# DC-DC.net
KiCad netlist of a schematic drawn in EAGLE
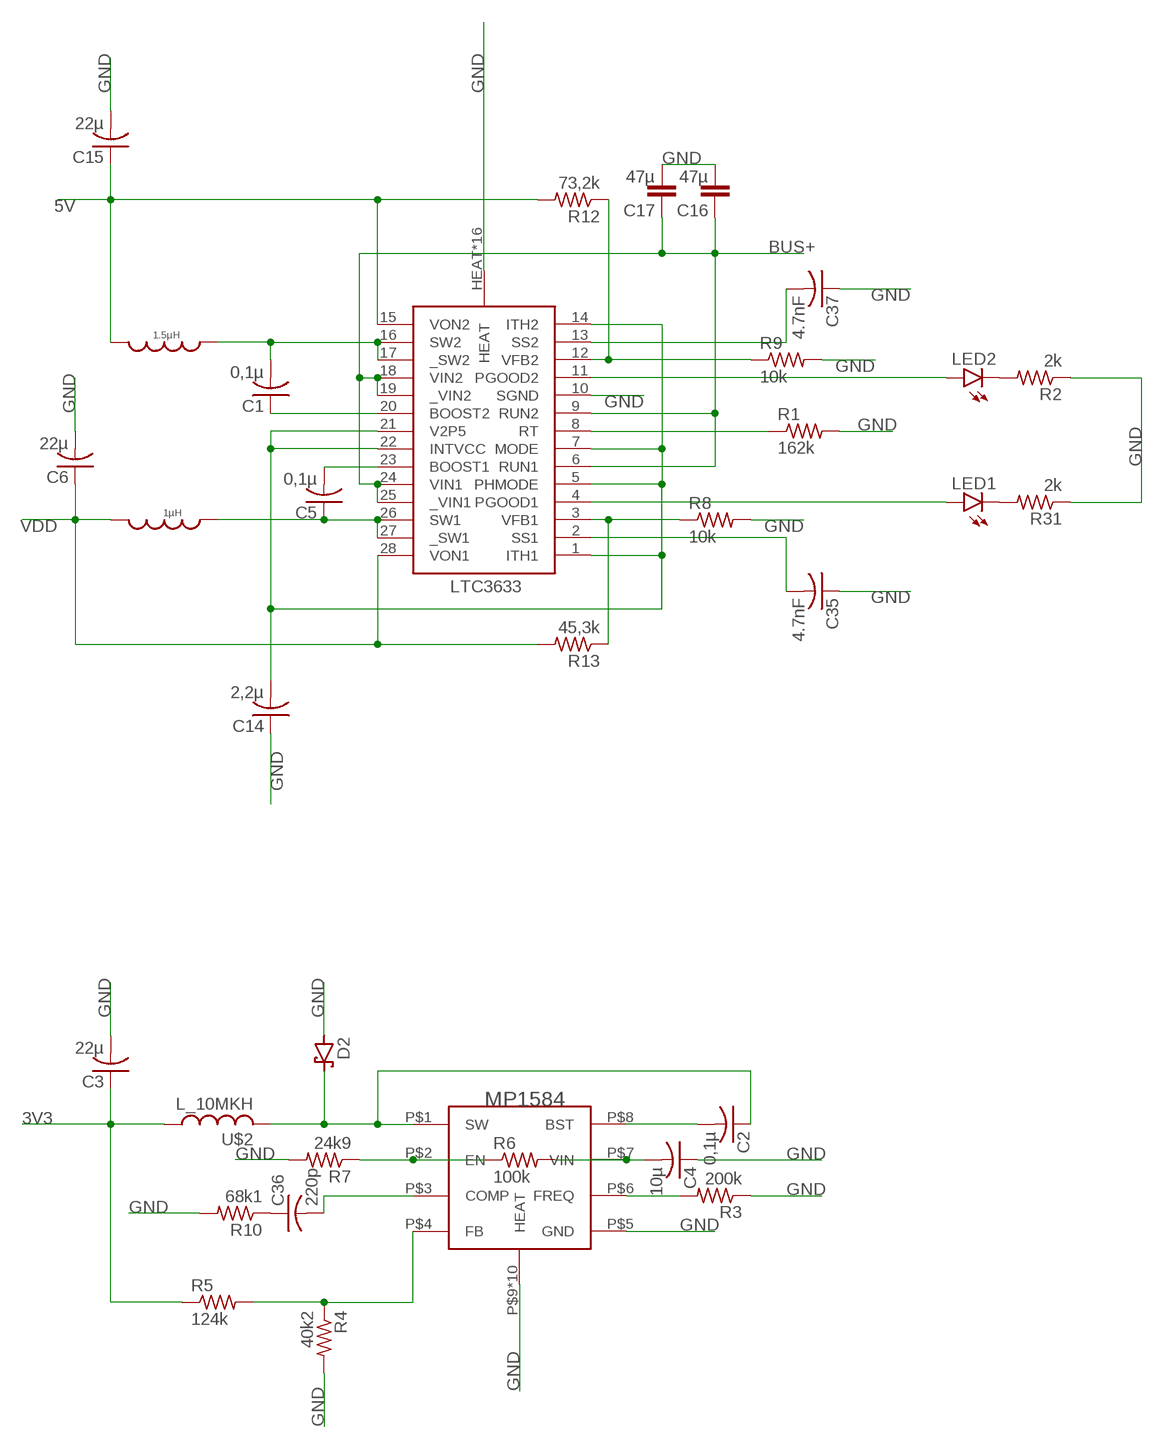
[diagram p0: schematic, sheet 1, part 1 of 3]
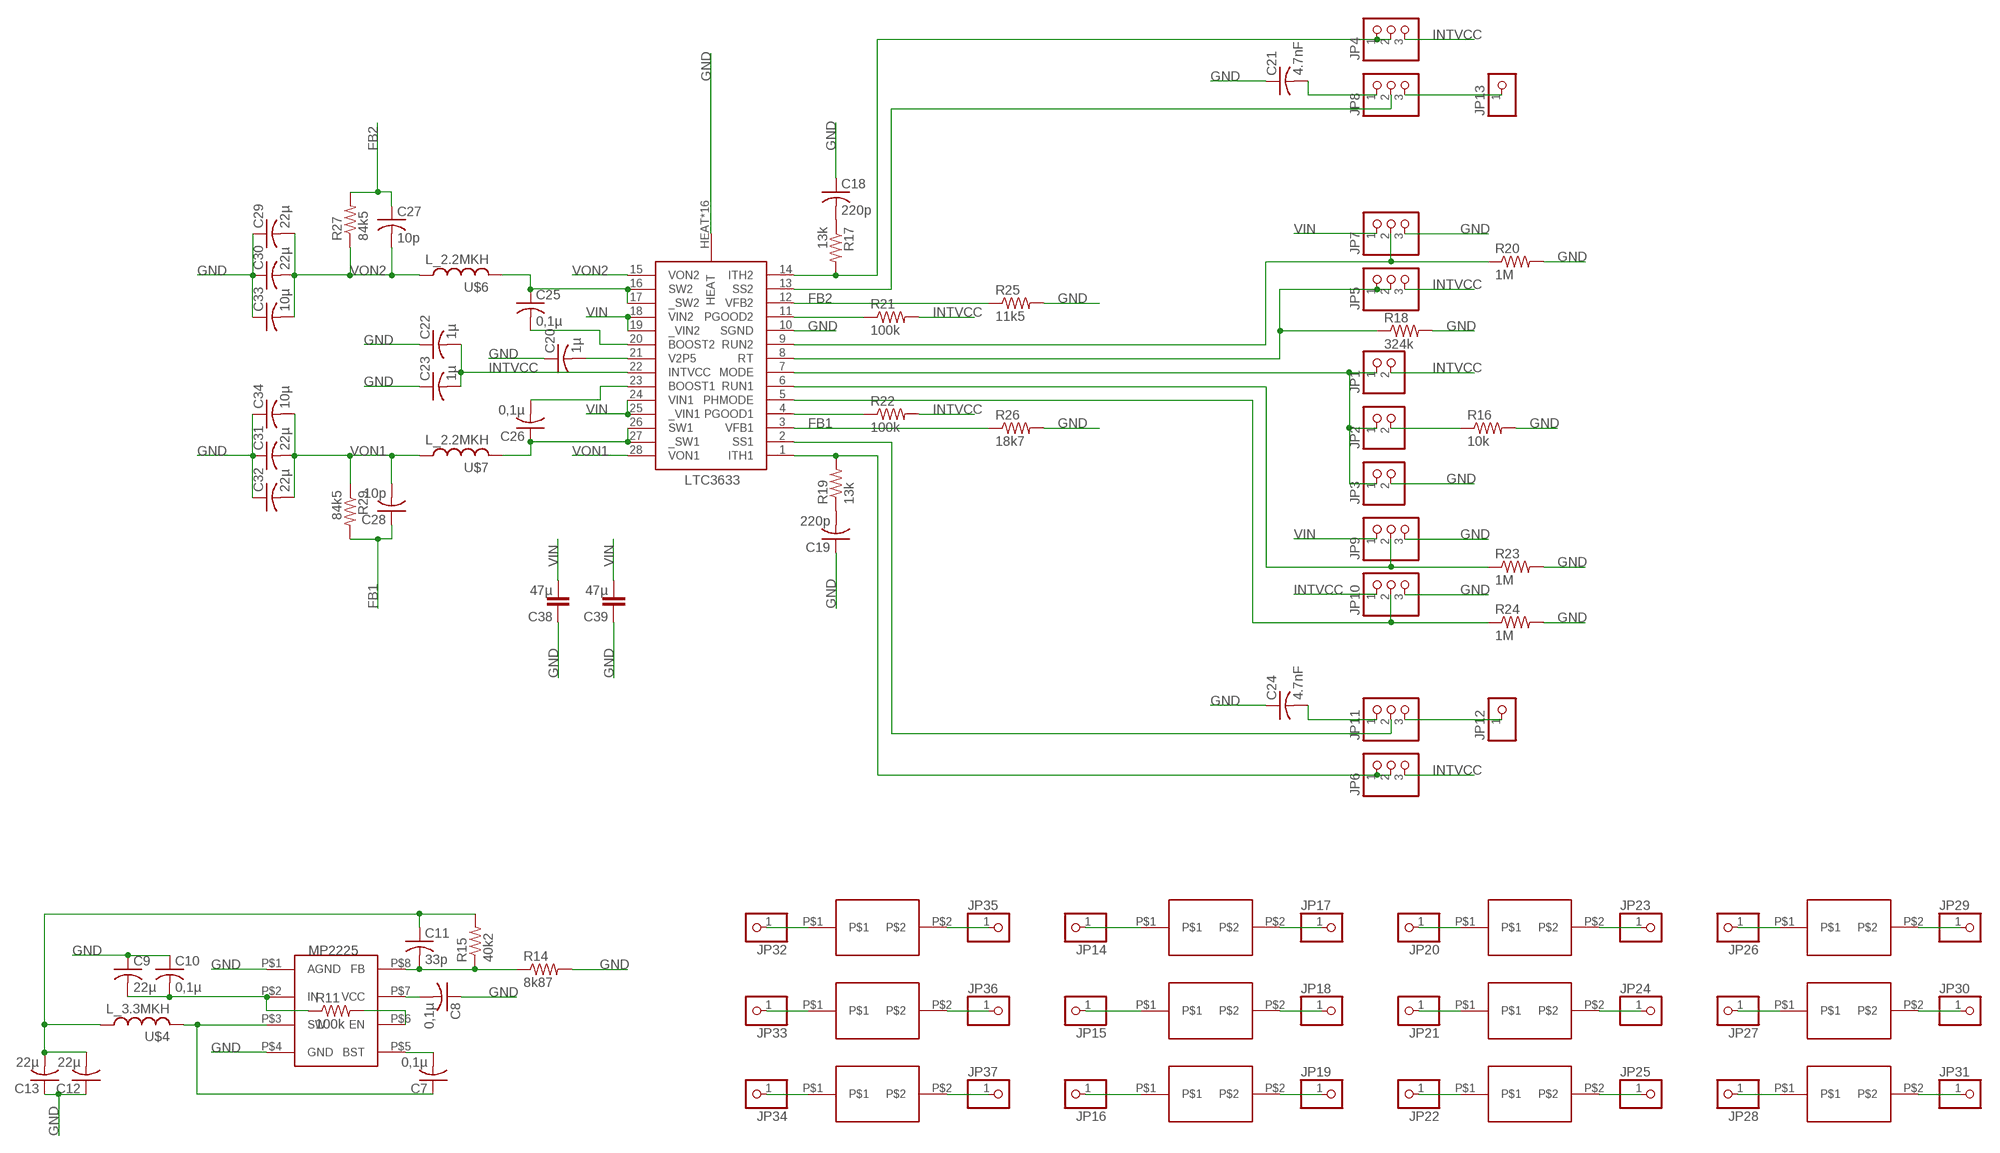
[diagram p1: schematic, sheet 1, part 2 of 3]
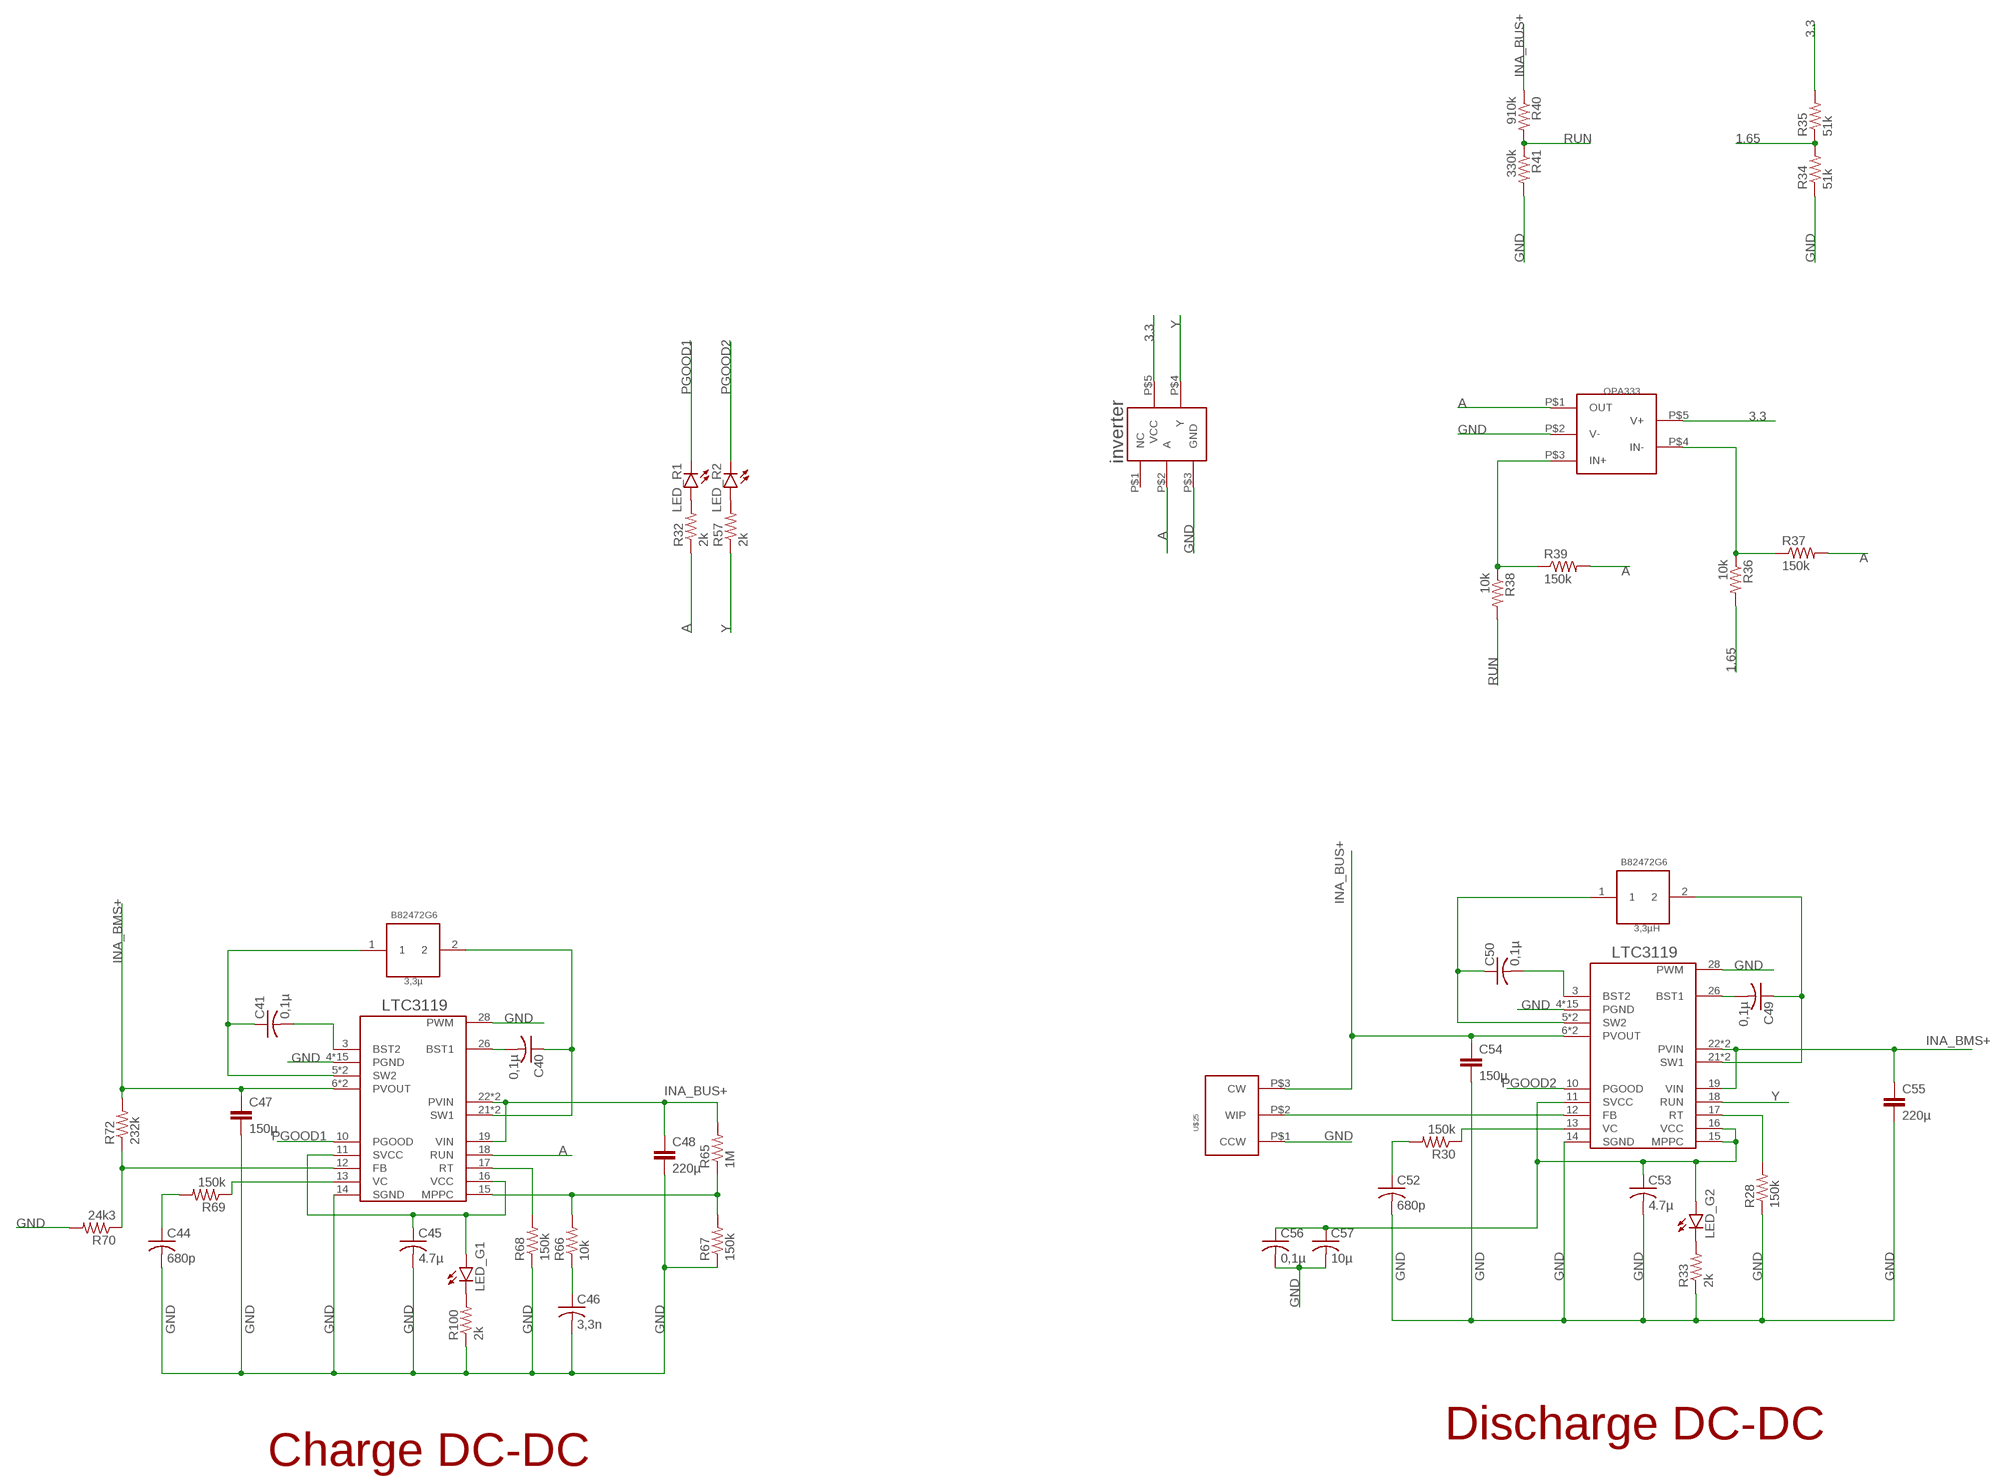
[diagram p2: schematic, sheet 1, part 3 of 3]

(export (version "E")
  (design (tool "Eeschema 10.0.6"))
  (components
    (comp (ref "3,3µH")
      (value "3,3µ")
      (footprint "eagle-import:B82472G6")
      (libsource (lib "eagle-import") (part "B82472G6"))
    )
    (comp (ref "3,3µH1")
      (value "3,3µH")
      (footprint "eagle-import:B82472G6")
      (libsource (lib "eagle-import") (part "B82472G6"))
    )
    (comp (ref "C1")
      (value "0,1µ")
      (footprint "eagle-import:C0603")
      (libsource (lib "eagle-import") (part "C-USC0603"))
    )
    (comp (ref "C2")
      (value "0,1µ")
      (footprint "eagle-import:C0603")
      (libsource (lib "eagle-import") (part "C-USC0603"))
    )
    (comp (ref "C3")
      (value "22µ")
      (footprint "eagle-import:C1206")
      (libsource (lib "eagle-import") (part "C-USC1206"))
    )
    (comp (ref "C4")
      (value "10µ")
      (footprint "eagle-import:C1206")
      (libsource (lib "eagle-import") (part "C-USC1206"))
    )
    (comp (ref "C5")
      (value "0,1µ")
      (footprint "eagle-import:C0603")
      (libsource (lib "eagle-import") (part "C-USC0603"))
    )
    (comp (ref "C6")
      (value "22µ")
      (footprint "eagle-import:C1206")
      (libsource (lib "eagle-import") (part "C-USC1206"))
    )
    (comp (ref "C7")
      (value "0,1µ")
      (footprint "eagle-import:C0603")
      (libsource (lib "eagle-import") (part "C-USC0603"))
    )
    (comp (ref "C8")
      (value "0,1µ")
      (footprint "eagle-import:C0603")
      (libsource (lib "eagle-import") (part "C-USC0603"))
    )
    (comp (ref "C9")
      (value "22µ")
      (footprint "eagle-import:C1206")
      (libsource (lib "eagle-import") (part "C-USC1206"))
    )
    (comp (ref "C10")
      (value "0,1µ")
      (footprint "eagle-import:C0603")
      (libsource (lib "eagle-import") (part "C-USC0603"))
    )
    (comp (ref "C11")
      (value "33p")
      (footprint "eagle-import:C0603")
      (libsource (lib "eagle-import") (part "C-USC0603"))
    )
    (comp (ref "C12")
      (value "22µ")
      (footprint "eagle-import:C1206")
      (libsource (lib "eagle-import") (part "C-USC1206"))
    )
    (comp (ref "C13")
      (value "22µ")
      (footprint "eagle-import:C1206")
      (libsource (lib "eagle-import") (part "C-USC1206"))
    )
    (comp (ref "C14")
      (value "2,2µ")
      (footprint "eagle-import:C0603")
      (libsource (lib "eagle-import") (part "C-USC0603"))
    )
    (comp (ref "C15")
      (value "22µ")
      (footprint "eagle-import:C1206")
      (libsource (lib "eagle-import") (part "C-USC1206"))
    )
    (comp (ref "C16")
      (value "47µ")
      (footprint "eagle-import:C1210")
      (libsource (lib "eagle-import") (part "C-EUC1210"))
    )
    (comp (ref "C17")
      (value "47µ")
      (footprint "eagle-import:C1210")
      (libsource (lib "eagle-import") (part "C-EUC1210"))
    )
    (comp (ref "C18")
      (value "220p")
      (footprint "eagle-import:C0603")
      (libsource (lib "eagle-import") (part "C-USC0603"))
    )
    (comp (ref "C19")
      (value "220p")
      (footprint "eagle-import:C0603")
      (libsource (lib "eagle-import") (part "C-USC0603"))
    )
    (comp (ref "C20")
      (value "1µ")
      (footprint "eagle-import:C0603")
      (libsource (lib "eagle-import") (part "C-USC0603"))
    )
    (comp (ref "C21")
      (value "4.7nF")
      (footprint "eagle-import:C0603")
      (libsource (lib "eagle-import") (part "C-USC0603"))
    )
    (comp (ref "C22")
      (value "1µ")
      (footprint "eagle-import:C0603")
      (libsource (lib "eagle-import") (part "C-USC0603"))
    )
    (comp (ref "C23")
      (value "1µ")
      (footprint "eagle-import:C0603")
      (libsource (lib "eagle-import") (part "C-USC0603"))
    )
    (comp (ref "C24")
      (value "4.7nF")
      (footprint "eagle-import:C0603")
      (libsource (lib "eagle-import") (part "C-USC0603"))
    )
    (comp (ref "C25")
      (value "0,1µ")
      (footprint "eagle-import:C0603")
      (libsource (lib "eagle-import") (part "C-USC0603"))
    )
    (comp (ref "C26")
      (value "0,1µ")
      (footprint "eagle-import:C0603")
      (libsource (lib "eagle-import") (part "C-USC0603"))
    )
    (comp (ref "C27")
      (value "10p")
      (footprint "eagle-import:C0603")
      (libsource (lib "eagle-import") (part "C-USC0603"))
    )
    (comp (ref "C28")
      (value "10p")
      (footprint "eagle-import:C0603")
      (libsource (lib "eagle-import") (part "C-USC0603"))
    )
    (comp (ref "C29")
      (value "22µ")
      (footprint "eagle-import:C1206")
      (libsource (lib "eagle-import") (part "C-USC1206"))
    )
    (comp (ref "C30")
      (value "22µ")
      (footprint "eagle-import:C1206")
      (libsource (lib "eagle-import") (part "C-USC1206"))
    )
    (comp (ref "C31")
      (value "22µ")
      (footprint "eagle-import:C1206")
      (libsource (lib "eagle-import") (part "C-USC1206"))
    )
    (comp (ref "C32")
      (value "22µ")
      (footprint "eagle-import:C1206")
      (libsource (lib "eagle-import") (part "C-USC1206"))
    )
    (comp (ref "C33")
      (value "10µ")
      (footprint "eagle-import:C1206")
      (libsource (lib "eagle-import") (part "C-USC1206"))
    )
    (comp (ref "C34")
      (value "10µ")
      (footprint "eagle-import:C1206")
      (libsource (lib "eagle-import") (part "C-USC1206"))
    )
    (comp (ref "C35")
      (value "4.7nF")
      (footprint "eagle-import:C0603")
      (libsource (lib "eagle-import") (part "C-USC0603"))
    )
    (comp (ref "C36")
      (value "220p")
      (footprint "eagle-import:C0603")
      (libsource (lib "eagle-import") (part "C-USC0603"))
    )
    (comp (ref "C37")
      (value "4.7nF")
      (footprint "eagle-import:C0603")
      (libsource (lib "eagle-import") (part "C-USC0603"))
    )
    (comp (ref "C38")
      (value "47µ")
      (footprint "eagle-import:C1210")
      (libsource (lib "eagle-import") (part "C-EUC1210"))
    )
    (comp (ref "C39")
      (value "47µ")
      (footprint "eagle-import:C1210")
      (libsource (lib "eagle-import") (part "C-EUC1210"))
    )
    (comp (ref "C40")
      (value "0,1µ")
      (footprint "eagle-import:C0603")
      (libsource (lib "eagle-import") (part "C-USC0603"))
    )
    (comp (ref "C41")
      (value "0,1µ")
      (footprint "eagle-import:C0603")
      (libsource (lib "eagle-import") (part "C-USC0603"))
    )
    (comp (ref "C44")
      (value "680p")
      (footprint "eagle-import:C0603")
      (libsource (lib "eagle-import") (part "C-USC0603"))
    )
    (comp (ref "C45")
      (value "4.7µ")
      (footprint "eagle-import:C1206")
      (libsource (lib "eagle-import") (part "C-USC1206"))
    )
    (comp (ref "C46")
      (value "3,3n")
      (footprint "eagle-import:C0603")
      (libsource (lib "eagle-import") (part "C-USC0603"))
    )
    (comp (ref "C47")
      (value "150µ")
      (footprint "eagle-import:ECAP150")
      (libsource (lib "eagle-import") (part "ECAPECAP150"))
    )
    (comp (ref "C48")
      (value "220µ")
      (footprint "eagle-import:ECAP220")
      (libsource (lib "eagle-import") (part "ECAPECAP220"))
    )
    (comp (ref "C49")
      (value "0,1µ")
      (footprint "eagle-import:C0603")
      (libsource (lib "eagle-import") (part "C-USC0603"))
    )
    (comp (ref "C50")
      (value "0,1µ")
      (footprint "eagle-import:C0603")
      (libsource (lib "eagle-import") (part "C-USC0603"))
    )
    (comp (ref "C52")
      (value "680p")
      (footprint "eagle-import:C0603")
      (libsource (lib "eagle-import") (part "C-USC0603"))
    )
    (comp (ref "C53")
      (value "4.7µ")
      (footprint "eagle-import:C1206")
      (libsource (lib "eagle-import") (part "C-USC1206"))
    )
    (comp (ref "C54")
      (value "150µ")
      (footprint "eagle-import:ECAP150")
      (libsource (lib "eagle-import") (part "ECAPECAP150"))
    )
    (comp (ref "C55")
      (value "220µ")
      (footprint "eagle-import:ECAP220")
      (libsource (lib "eagle-import") (part "ECAPECAP220"))
    )
    (comp (ref "C56")
      (value "0,1µ")
      (footprint "eagle-import:C0603")
      (libsource (lib "eagle-import") (part "C-USC0603"))
    )
    (comp (ref "C57")
      (value "10µ")
      (footprint "eagle-import:C1206")
      (libsource (lib "eagle-import") (part "C-USC1206"))
    )
    (comp (ref "D2")
      (value "SCHOTTKY-DIODESMC")
      (footprint "eagle-import:SMC")
      (libsource (lib "eagle-import") (part "SCHOTTKY-DIODESMC"))
    )
    (comp (ref "INVERT")
      (value "INVERTER")
      (footprint "eagle-import:SOT23-5")
      (libsource (lib "eagle-import") (part "INVERTER"))
    )
    (comp (ref "JP1")
      (value "PINHD-1X2")
      (footprint "eagle-import:1X02")
      (libsource (lib "eagle-import") (part "PINHD-1X2"))
    )
    (comp (ref "JP2")
      (value "PINHD-1X2")
      (footprint "eagle-import:1X02")
      (libsource (lib "eagle-import") (part "PINHD-1X2"))
    )
    (comp (ref "JP3")
      (value "PINHD-1X2")
      (footprint "eagle-import:1X02")
      (libsource (lib "eagle-import") (part "PINHD-1X2"))
    )
    (comp (ref "JP4")
      (value "PINHD-1X3")
      (footprint "eagle-import:1X03")
      (libsource (lib "eagle-import") (part "PINHD-1X3"))
    )
    (comp (ref "JP5")
      (value "PINHD-1X3")
      (footprint "eagle-import:1X03")
      (libsource (lib "eagle-import") (part "PINHD-1X3"))
    )
    (comp (ref "JP6")
      (value "PINHD-1X3")
      (footprint "eagle-import:1X03")
      (libsource (lib "eagle-import") (part "PINHD-1X3"))
    )
    (comp (ref "JP7")
      (value "PINHD-1X3")
      (footprint "eagle-import:1X03")
      (libsource (lib "eagle-import") (part "PINHD-1X3"))
    )
    (comp (ref "JP8")
      (value "PINHD-1X3")
      (footprint "eagle-import:1X03")
      (libsource (lib "eagle-import") (part "PINHD-1X3"))
    )
    (comp (ref "JP9")
      (value "PINHD-1X3")
      (footprint "eagle-import:1X03")
      (libsource (lib "eagle-import") (part "PINHD-1X3"))
    )
    (comp (ref "JP10")
      (value "PINHD-1X3")
      (footprint "eagle-import:1X03")
      (libsource (lib "eagle-import") (part "PINHD-1X3"))
    )
    (comp (ref "JP11")
      (value "PINHD-1X3")
      (footprint "eagle-import:1X03")
      (libsource (lib "eagle-import") (part "PINHD-1X3"))
    )
    (comp (ref "JP12")
      (value "PINHD-1X1")
      (footprint "eagle-import:1X01")
      (libsource (lib "eagle-import") (part "PINHD-1X1"))
    )
    (comp (ref "JP13")
      (value "PINHD-1X1")
      (footprint "eagle-import:1X01")
      (libsource (lib "eagle-import") (part "PINHD-1X1"))
    )
    (comp (ref "JP14")
      (value "PINHD-1X1")
      (footprint "eagle-import:1X01")
      (libsource (lib "eagle-import") (part "PINHD-1X1"))
    )
    (comp (ref "JP15")
      (value "PINHD-1X1")
      (footprint "eagle-import:1X01")
      (libsource (lib "eagle-import") (part "PINHD-1X1"))
    )
    (comp (ref "JP16")
      (value "PINHD-1X1")
      (footprint "eagle-import:1X01")
      (libsource (lib "eagle-import") (part "PINHD-1X1"))
    )
    (comp (ref "JP17")
      (value "PINHD-1X1")
      (footprint "eagle-import:1X01")
      (libsource (lib "eagle-import") (part "PINHD-1X1"))
    )
    (comp (ref "JP18")
      (value "PINHD-1X1")
      (footprint "eagle-import:1X01")
      (libsource (lib "eagle-import") (part "PINHD-1X1"))
    )
    (comp (ref "JP19")
      (value "PINHD-1X1")
      (footprint "eagle-import:1X01")
      (libsource (lib "eagle-import") (part "PINHD-1X1"))
    )
    (comp (ref "JP20")
      (value "PINHD-1X1")
      (footprint "eagle-import:1X01")
      (libsource (lib "eagle-import") (part "PINHD-1X1"))
    )
    (comp (ref "JP21")
      (value "PINHD-1X1")
      (footprint "eagle-import:1X01")
      (libsource (lib "eagle-import") (part "PINHD-1X1"))
    )
    (comp (ref "JP22")
      (value "PINHD-1X1")
      (footprint "eagle-import:1X01")
      (libsource (lib "eagle-import") (part "PINHD-1X1"))
    )
    (comp (ref "JP23")
      (value "PINHD-1X1")
      (footprint "eagle-import:1X01")
      (libsource (lib "eagle-import") (part "PINHD-1X1"))
    )
    (comp (ref "JP24")
      (value "PINHD-1X1")
      (footprint "eagle-import:1X01")
      (libsource (lib "eagle-import") (part "PINHD-1X1"))
    )
    (comp (ref "JP25")
      (value "PINHD-1X1")
      (footprint "eagle-import:1X01")
      (libsource (lib "eagle-import") (part "PINHD-1X1"))
    )
    (comp (ref "JP26")
      (value "PINHD-1X1")
      (footprint "eagle-import:1X01")
      (libsource (lib "eagle-import") (part "PINHD-1X1"))
    )
    (comp (ref "JP27")
      (value "PINHD-1X1")
      (footprint "eagle-import:1X01")
      (libsource (lib "eagle-import") (part "PINHD-1X1"))
    )
    (comp (ref "JP28")
      (value "PINHD-1X1")
      (footprint "eagle-import:1X01")
      (libsource (lib "eagle-import") (part "PINHD-1X1"))
    )
    (comp (ref "JP29")
      (value "PINHD-1X1")
      (footprint "eagle-import:1X01")
      (libsource (lib "eagle-import") (part "PINHD-1X1"))
    )
    (comp (ref "JP30")
      (value "PINHD-1X1")
      (footprint "eagle-import:1X01")
      (libsource (lib "eagle-import") (part "PINHD-1X1"))
    )
    (comp (ref "JP31")
      (value "PINHD-1X1")
      (footprint "eagle-import:1X01")
      (libsource (lib "eagle-import") (part "PINHD-1X1"))
    )
    (comp (ref "JP32")
      (value "PINHD-1X1")
      (footprint "eagle-import:1X01")
      (libsource (lib "eagle-import") (part "PINHD-1X1"))
    )
    (comp (ref "JP33")
      (value "PINHD-1X1")
      (footprint "eagle-import:1X01")
      (libsource (lib "eagle-import") (part "PINHD-1X1"))
    )
    (comp (ref "JP34")
      (value "PINHD-1X1")
      (footprint "eagle-import:1X01")
      (libsource (lib "eagle-import") (part "PINHD-1X1"))
    )
    (comp (ref "JP35")
      (value "PINHD-1X1")
      (footprint "eagle-import:1X01")
      (libsource (lib "eagle-import") (part "PINHD-1X1"))
    )
    (comp (ref "JP36")
      (value "PINHD-1X1")
      (footprint "eagle-import:1X01")
      (libsource (lib "eagle-import") (part "PINHD-1X1"))
    )
    (comp (ref "JP37")
      (value "PINHD-1X1")
      (footprint "eagle-import:1X01")
      (libsource (lib "eagle-import") (part "PINHD-1X1"))
    )
    (comp (ref "LED1")
      (value "LEDCHIPLED_0603")
      (footprint "eagle-import:CHIPLED_0603")
      (libsource (lib "eagle-import") (part "LEDCHIPLED_0603"))
    )
    (comp (ref "LED2")
      (value "LEDCHIPLED_0603")
      (footprint "eagle-import:CHIPLED_0603")
      (libsource (lib "eagle-import") (part "LEDCHIPLED_0603"))
    )
    (comp (ref "LED_G1")
      (value "LEDCHIPLED_0603")
      (footprint "eagle-import:CHIPLED_0603")
      (libsource (lib "eagle-import") (part "LEDCHIPLED_0603"))
    )
    (comp (ref "LED_G2")
      (value "LEDCHIPLED_0603")
      (footprint "eagle-import:CHIPLED_0603")
      (libsource (lib "eagle-import") (part "LEDCHIPLED_0603"))
    )
    (comp (ref "LED_R1")
      (value "LEDCHIPLED_0603")
      (footprint "eagle-import:CHIPLED_0603")
      (libsource (lib "eagle-import") (part "LEDCHIPLED_0603"))
    )
    (comp (ref "LED_R2")
      (value "LEDCHIPLED_0603")
      (footprint "eagle-import:CHIPLED_0603")
      (libsource (lib "eagle-import") (part "LEDCHIPLED_0603"))
    )
    (comp (ref "OPA")
      (value "OPA333")
      (footprint "eagle-import:SOT23-5")
      (libsource (lib "eagle-import") (part "OPA333"))
    )
    (comp (ref "R1")
      (value "162k")
      (footprint "eagle-import:R0603")
      (libsource (lib "eagle-import") (part "R-US_R0603"))
    )
    (comp (ref "R2")
      (value "2k")
      (footprint "eagle-import:R0603")
      (libsource (lib "eagle-import") (part "R-US_R0603"))
    )
    (comp (ref "R3")
      (value "200k")
      (footprint "eagle-import:R0603")
      (libsource (lib "eagle-import") (part "R-US_R0603"))
    )
    (comp (ref "R4")
      (value "40k2")
      (footprint "eagle-import:R0603")
      (libsource (lib "eagle-import") (part "R-US_R0603"))
    )
    (comp (ref "R5")
      (value "124k")
      (footprint "eagle-import:R0603")
      (libsource (lib "eagle-import") (part "R-US_R0603"))
    )
    (comp (ref "R6")
      (value "100k")
      (footprint "eagle-import:R0603")
      (libsource (lib "eagle-import") (part "R-US_R0603"))
    )
    (comp (ref "R7")
      (value "24k9")
      (footprint "eagle-import:R0603")
      (libsource (lib "eagle-import") (part "R-US_R0603"))
    )
    (comp (ref "R8")
      (value "10k")
      (footprint "eagle-import:R0603")
      (libsource (lib "eagle-import") (part "R-US_R0603"))
    )
    (comp (ref "R9")
      (value "10k")
      (footprint "eagle-import:R0603")
      (libsource (lib "eagle-import") (part "R-US_R0603"))
    )
    (comp (ref "R10")
      (value "68k1")
      (footprint "eagle-import:R0603")
      (libsource (lib "eagle-import") (part "R-US_R0603"))
    )
    (comp (ref "R11")
      (value "100k")
      (footprint "eagle-import:R0603")
      (libsource (lib "eagle-import") (part "R-US_R0603"))
    )
    (comp (ref "R12")
      (value "73,2k")
      (footprint "eagle-import:R0603")
      (libsource (lib "eagle-import") (part "R-US_R0603"))
    )
    (comp (ref "R13")
      (value "45,3k")
      (footprint "eagle-import:R0603")
      (libsource (lib "eagle-import") (part "R-US_R0603"))
    )
    (comp (ref "R14")
      (value "8k87")
      (footprint "eagle-import:R0603")
      (libsource (lib "eagle-import") (part "R-US_R0603"))
    )
    (comp (ref "R15")
      (value "40k2")
      (footprint "eagle-import:R0603")
      (libsource (lib "eagle-import") (part "R-US_R0603"))
    )
    (comp (ref "R16")
      (value "10k")
      (footprint "eagle-import:R0603")
      (libsource (lib "eagle-import") (part "R-US_R0603"))
    )
    (comp (ref "R17")
      (value "13k")
      (footprint "eagle-import:R0603")
      (libsource (lib "eagle-import") (part "R-US_R0603"))
    )
    (comp (ref "R18")
      (value "324k")
      (footprint "eagle-import:R0603")
      (libsource (lib "eagle-import") (part "R-US_R0603"))
    )
    (comp (ref "R19")
      (value "13k")
      (footprint "eagle-import:R0603")
      (libsource (lib "eagle-import") (part "R-US_R0603"))
    )
    (comp (ref "R20")
      (value "1M")
      (footprint "eagle-import:R0603")
      (libsource (lib "eagle-import") (part "R-US_R0603"))
    )
    (comp (ref "R21")
      (value "100k")
      (footprint "eagle-import:R0603")
      (libsource (lib "eagle-import") (part "R-US_R0603"))
    )
    (comp (ref "R22")
      (value "100k")
      (footprint "eagle-import:R0603")
      (libsource (lib "eagle-import") (part "R-US_R0603"))
    )
    (comp (ref "R23")
      (value "1M")
      (footprint "eagle-import:R0603")
      (libsource (lib "eagle-import") (part "R-US_R0603"))
    )
    (comp (ref "R24")
      (value "1M")
      (footprint "eagle-import:R0603")
      (libsource (lib "eagle-import") (part "R-US_R0603"))
    )
    (comp (ref "R25")
      (value "11k5")
      (footprint "eagle-import:R0603")
      (libsource (lib "eagle-import") (part "R-US_R0603"))
    )
    (comp (ref "R26")
      (value "18k7")
      (footprint "eagle-import:R0603")
      (libsource (lib "eagle-import") (part "R-US_R0603"))
    )
    (comp (ref "R27")
      (value "84k5")
      (footprint "eagle-import:R0603")
      (libsource (lib "eagle-import") (part "R-US_R0603"))
    )
    (comp (ref "R28")
      (value "150k")
      (footprint "eagle-import:R0603")
      (libsource (lib "eagle-import") (part "R-US_R0603"))
    )
    (comp (ref "R29")
      (value "84k5")
      (footprint "eagle-import:R0603")
      (libsource (lib "eagle-import") (part "R-US_R0603"))
    )
    (comp (ref "R30")
      (value "150k")
      (footprint "eagle-import:R0603")
      (libsource (lib "eagle-import") (part "R-US_R0603"))
    )
    (comp (ref "R31")
      (value "2k")
      (footprint "eagle-import:R0603")
      (libsource (lib "eagle-import") (part "R-US_R0603"))
    )
    (comp (ref "R32")
      (value "2k")
      (footprint "eagle-import:R0603")
      (libsource (lib "eagle-import") (part "R-US_R0603"))
    )
    (comp (ref "R33")
      (value "2k")
      (footprint "eagle-import:R0603")
      (libsource (lib "eagle-import") (part "R-US_R0603"))
    )
    (comp (ref "R34")
      (value "51k")
      (footprint "eagle-import:R0603")
      (libsource (lib "eagle-import") (part "R-US_R0603"))
    )
    (comp (ref "R35")
      (value "51k")
      (footprint "eagle-import:R0603")
      (libsource (lib "eagle-import") (part "R-US_R0603"))
    )
    (comp (ref "R36")
      (value "10k")
      (footprint "eagle-import:R0603")
      (libsource (lib "eagle-import") (part "R-US_R0603"))
    )
    (comp (ref "R37")
      (value "150k")
      (footprint "eagle-import:R0603")
      (libsource (lib "eagle-import") (part "R-US_R0603"))
    )
    (comp (ref "R38")
      (value "10k")
      (footprint "eagle-import:R0603")
      (libsource (lib "eagle-import") (part "R-US_R0603"))
    )
    (comp (ref "R39")
      (value "150k")
      (footprint "eagle-import:R0603")
      (libsource (lib "eagle-import") (part "R-US_R0603"))
    )
    (comp (ref "R40")
      (value "910k")
      (footprint "eagle-import:R0603")
      (libsource (lib "eagle-import") (part "R-US_R0603"))
    )
    (comp (ref "R41")
      (value "330k")
      (footprint "eagle-import:R0603")
      (libsource (lib "eagle-import") (part "R-US_R0603"))
    )
    (comp (ref "R57")
      (value "2k")
      (footprint "eagle-import:R0603")
      (libsource (lib "eagle-import") (part "R-US_R0603"))
    )
    (comp (ref "R65")
      (value "1M")
      (footprint "eagle-import:R0603")
      (libsource (lib "eagle-import") (part "R-US_R0603"))
    )
    (comp (ref "R66")
      (value "10k")
      (footprint "eagle-import:R0603")
      (libsource (lib "eagle-import") (part "R-US_R0603"))
    )
    (comp (ref "R67")
      (value "150k")
      (footprint "eagle-import:R0603")
      (libsource (lib "eagle-import") (part "R-US_R0603"))
    )
    (comp (ref "R68")
      (value "150k")
      (footprint "eagle-import:R0603")
      (libsource (lib "eagle-import") (part "R-US_R0603"))
    )
    (comp (ref "R69")
      (value "150k")
      (footprint "eagle-import:R0603")
      (libsource (lib "eagle-import") (part "R-US_R0603"))
    )
    (comp (ref "R70")
      (value "24k3")
      (footprint "eagle-import:R0603")
      (libsource (lib "eagle-import") (part "R-US_R0603"))
    )
    (comp (ref "R72")
      (value "232k")
      (footprint "eagle-import:R0603")
      (libsource (lib "eagle-import") (part "R-US_R0603"))
    )
    (comp (ref "R100")
      (value "2k")
      (footprint "eagle-import:R0603")
      (libsource (lib "eagle-import") (part "R-US_R0603"))
    )
    (comp (ref "U$1")
      (value "MP1584+VIA")
      (footprint "eagle-import:MP1584+VIA")
      (libsource (lib "eagle-import") (part "MP1584+VIA"))
    )
    (comp (ref "U$2")
      (value "L_10MKH")
      (footprint "eagle-import:L_12X12")
      (libsource (lib "eagle-import") (part "L_10MKH"))
    )
    (comp (ref "U$3")
      (value "MP2225")
      (footprint "eagle-import:TSOT23-8")
      (libsource (lib "eagle-import") (part "MP2225"))
    )
    (comp (ref "U$4")
      (value "L_3.3MKH")
      (footprint "eagle-import:L_SPM5020")
      (libsource (lib "eagle-import") (part "L_3.3MKH_5X5"))
    )
    (comp (ref "U$5")
      (value "LTC3633+VIA")
      (footprint "eagle-import:LTC3633+VIA")
      (libsource (lib "eagle-import") (part "LTC3633+VIA"))
    )
    (comp (ref "U$6")
      (value "L_2.2MKH")
      (footprint "eagle-import:L_SPM4020")
      (libsource (lib "eagle-import") (part "L_2.2MKH"))
    )
    (comp (ref "U$7")
      (value "L_2.2MKH")
      (footprint "eagle-import:L_SPM4020")
      (libsource (lib "eagle-import") (part "L_2.2MKH"))
    )
    (comp (ref "U$8")
      (value "GRAFITGRAFIT1")
      (footprint "eagle-import:GRAFIT1")
      (libsource (lib "eagle-import") (part "GRAFITGRAFIT1"))
    )
    (comp (ref "U$9")
      (value "GRAFITGRAFIT1_1")
      (footprint "eagle-import:GRAFIT1_1")
      (libsource (lib "eagle-import") (part "GRAFITGRAFIT1_1"))
    )
    (comp (ref "U$10")
      (value "LTC3633+VIA")
      (footprint "eagle-import:LTC3633+VIA")
      (libsource (lib "eagle-import") (part "LTC3633+VIA"))
    )
    (comp (ref "U$11")
      (value "1µH")
      (footprint "eagle-import:VLS3012HBX")
      (libsource (lib "eagle-import") (part "VLS3012HBX"))
    )
    (comp (ref "U$12")
      (value "SPM4020")
      (footprint "eagle-import:SPM4020")
      (libsource (lib "eagle-import") (part "SPM4020"))
    )
    (comp (ref "U$13")
      (value "GRAFITGRAFIT1_2")
      (footprint "eagle-import:GRAFIT1_2")
      (libsource (lib "eagle-import") (part "GRAFITGRAFIT1_2"))
    )
    (comp (ref "U$14")
      (value "GRAFITGRAFIT2")
      (footprint "eagle-import:GRAFIT2")
      (libsource (lib "eagle-import") (part "GRAFITGRAFIT2"))
    )
    (comp (ref "U$15")
      (value "GRAFITGRAFIT2_1")
      (footprint "eagle-import:GRAFIT2_1")
      (libsource (lib "eagle-import") (part "GRAFITGRAFIT2_1"))
    )
    (comp (ref "U$16")
      (value "GRAFITGRAFIT2_2")
      (footprint "eagle-import:GRAFIT2_2")
      (libsource (lib "eagle-import") (part "GRAFITGRAFIT2_2"))
    )
    (comp (ref "U$17")
      (value "GRAFITGRAFIT3")
      (footprint "eagle-import:GRAFIT3")
      (libsource (lib "eagle-import") (part "GRAFITGRAFIT3"))
    )
    (comp (ref "U$18")
      (value "GRAFITGRAFIT3_1")
      (footprint "eagle-import:GRAFIT3_1")
      (libsource (lib "eagle-import") (part "GRAFITGRAFIT3_1"))
    )
    (comp (ref "U$19")
      (value "GRAFITGRAFIT3_2")
      (footprint "eagle-import:GRAFIT3_2")
      (libsource (lib "eagle-import") (part "GRAFITGRAFIT3_2"))
    )
    (comp (ref "U$20")
      (value "GRAFITGRAFIT4")
      (footprint "eagle-import:GRAFIT4")
      (libsource (lib "eagle-import") (part "GRAFITGRAFIT4"))
    )
    (comp (ref "U$21")
      (value "GRAFITGRAFIT4_1")
      (footprint "eagle-import:GRAFIT4_1")
      (libsource (lib "eagle-import") (part "GRAFITGRAFIT4_1"))
    )
    (comp (ref "U$22")
      (value "GRAFITGRAFIT4_2")
      (footprint "eagle-import:GRAFIT4_2")
      (libsource (lib "eagle-import") (part "GRAFITGRAFIT4_2"))
    )
    (comp (ref "U$23")
      (value "LTC31191")
      (footprint "eagle-import:LTC3119+VIA")
      (libsource (lib "eagle-import") (part "LTC31191"))
    )
    (comp (ref "U$25")
      (value "32961")
      (footprint "eagle-import:3296W")
      (libsource (lib "eagle-import") (part "32961"))
    )
    (comp (ref "U$59")
      (value "LTC31191")
      (footprint "eagle-import:LTC3119+VIA")
      (libsource (lib "eagle-import") (part "LTC31191"))
    )
  )
  (nets
    (net (code "1") (name "/1.65") (class "Default")
      (node (ref "R34") (pin "2") (pinfunction "2_2") (pintype "passive"))
      (node (ref "R35") (pin "1") (pinfunction "1_1") (pintype "passive"))
      (node (ref "R36") (pin "2") (pinfunction "2_2") (pintype "passive"))
    )
    (net (code "2") (name "/3.3") (class "Default")
      (node (ref "INVERT") (pin "P$5") (pinfunction "VCC_P$5") (pintype "bidirectional"))
      (node (ref "OPA") (pin "P$5") (pinfunction "V+_P$5") (pintype "bidirectional"))
      (node (ref "R35") (pin "2") (pinfunction "2_2") (pintype "passive"))
    )
    (net (code "3") (name "/3V3") (class "Default")
      (node (ref "C3") (pin "1") (pinfunction "1_1") (pintype "passive"))
      (node (ref "R5") (pin "1") (pinfunction "1_1") (pintype "passive"))
      (node (ref "U$2") (pin "P$1") (pinfunction "1_P$1") (pintype "passive"))
    )
    (net (code "4") (name "/5V") (class "Default")
      (node (ref "C15") (pin "1") (pinfunction "1_1") (pintype "passive"))
      (node (ref "R12") (pin "2") (pinfunction "2_2") (pintype "passive"))
      (node (ref "U$10") (pin "15") (pinfunction "VON2_15") (pintype "bidirectional"))
      (node (ref "U$12") (pin "P$2") (pinfunction "2_P$2") (pintype "passive"))
    )
    (net (code "5") (name "/A") (class "Default")
      (node (ref "INVERT") (pin "P$2") (pinfunction "A_P$2") (pintype "bidirectional"))
      (node (ref "OPA") (pin "P$1") (pinfunction "OUT_P$1") (pintype "bidirectional"))
      (node (ref "R32") (pin "1") (pinfunction "1_1") (pintype "passive"))
      (node (ref "R37") (pin "2") (pinfunction "2_2") (pintype "passive"))
      (node (ref "R39") (pin "2") (pinfunction "2_2") (pintype "passive"))
      (node (ref "U$59") (pin "18") (pinfunction "RUN_18") (pintype "bidirectional"))
    )
    (net (code "6") (name "/BUS+") (class "Default")
      (node (ref "C16") (pin "1") (pinfunction "1_1") (pintype "passive"))
      (node (ref "C17") (pin "1") (pinfunction "1_1") (pintype "passive"))
      (node (ref "U$10") (pin "18") (pinfunction "VIN2_18") (pintype "bidirectional"))
      (node (ref "U$10") (pin "19") (pinfunction "_VIN2_19") (pintype "bidirectional"))
      (node (ref "U$10") (pin "24") (pinfunction "VIN1_24") (pintype "bidirectional"))
      (node (ref "U$10") (pin "25") (pinfunction "_VIN1_25") (pintype "bidirectional"))
      (node (ref "U$10") (pin "6") (pinfunction "RUN1_6") (pintype "bidirectional"))
      (node (ref "U$10") (pin "9") (pinfunction "RUN2_9") (pintype "bidirectional"))
    )
    (net (code "7") (name "/FB1") (class "Default")
      (node (ref "C28") (pin "1") (pinfunction "1_1") (pintype "passive"))
      (node (ref "R26") (pin "1") (pinfunction "1_1") (pintype "passive"))
      (node (ref "R29") (pin "2") (pinfunction "2_2") (pintype "passive"))
      (node (ref "U$5") (pin "3") (pinfunction "VFB1_3") (pintype "bidirectional"))
    )
    (net (code "8") (name "/FB2") (class "Default")
      (node (ref "C27") (pin "1") (pinfunction "1_1") (pintype "passive"))
      (node (ref "R25") (pin "1") (pinfunction "1_1") (pintype "passive"))
      (node (ref "R27") (pin "2") (pinfunction "2_2") (pintype "passive"))
      (node (ref "U$5") (pin "12") (pinfunction "VFB2_12") (pintype "bidirectional"))
    )
    (net (code "9") (name "/GND") (class "Default")
      (node (ref "C10") (pin "1") (pinfunction "1_1") (pintype "passive"))
      (node (ref "C12") (pin "1") (pinfunction "1_1") (pintype "passive"))
      (node (ref "C13") (pin "1") (pinfunction "1_1") (pintype "passive"))
      (node (ref "C14") (pin "1") (pinfunction "1_1") (pintype "passive"))
      (node (ref "C15") (pin "2") (pinfunction "2_2") (pintype "passive"))
      (node (ref "C16") (pin "2") (pinfunction "2_2") (pintype "passive"))
      (node (ref "C17") (pin "2") (pinfunction "2_2") (pintype "passive"))
      (node (ref "C18") (pin "1") (pinfunction "1_1") (pintype "passive"))
      (node (ref "C19") (pin "1") (pinfunction "1_1") (pintype "passive"))
      (node (ref "C20") (pin "1") (pinfunction "1_1") (pintype "passive"))
      (node (ref "C21") (pin "1") (pinfunction "1_1") (pintype "passive"))
      (node (ref "C22") (pin "1") (pinfunction "1_1") (pintype "passive"))
      (node (ref "C23") (pin "1") (pinfunction "1_1") (pintype "passive"))
      (node (ref "C24") (pin "1") (pinfunction "1_1") (pintype "passive"))
      (node (ref "C29") (pin "1") (pinfunction "1_1") (pintype "passive"))
      (node (ref "C3") (pin "2") (pinfunction "2_2") (pintype "passive"))
      (node (ref "C30") (pin "1") (pinfunction "1_1") (pintype "passive"))
      (node (ref "C31") (pin "1") (pinfunction "1_1") (pintype "passive"))
      (node (ref "C32") (pin "1") (pinfunction "1_1") (pintype "passive"))
      (node (ref "C33") (pin "1") (pinfunction "1_1") (pintype "passive"))
      (node (ref "C34") (pin "1") (pinfunction "1_1") (pintype "passive"))
      (node (ref "C35") (pin "1") (pinfunction "1_1") (pintype "passive"))
      (node (ref "C37") (pin "1") (pinfunction "1_1") (pintype "passive"))
      (node (ref "C38") (pin "1") (pinfunction "1_1") (pintype "passive"))
      (node (ref "C39") (pin "1") (pinfunction "1_1") (pintype "passive"))
      (node (ref "C4") (pin "1") (pinfunction "1_1") (pintype "passive"))
      (node (ref "C44") (pin "2") (pinfunction "2_2") (pintype "passive"))
      (node (ref "C45") (pin "2") (pinfunction "2_2") (pintype "passive"))
      (node (ref "C46") (pin "2") (pinfunction "2_2") (pintype "passive"))
      (node (ref "C47") (pin "P$2") (pinfunction "2_P$2") (pintype "passive"))
      (node (ref "C48") (pin "P$2") (pinfunction "2_P$2") (pintype "passive"))
      (node (ref "C52") (pin "2") (pinfunction "2_2") (pintype "passive"))
      (node (ref "C53") (pin "2") (pinfunction "2_2") (pintype "passive"))
      (node (ref "C54") (pin "P$2") (pinfunction "2_P$2") (pintype "passive"))
      (node (ref "C55") (pin "P$2") (pinfunction "2_P$2") (pintype "passive"))
      (node (ref "C56") (pin "2") (pinfunction "2_2") (pintype "passive"))
      (node (ref "C57") (pin "2") (pinfunction "2_2") (pintype "passive"))
      (node (ref "C6") (pin "2") (pinfunction "2_2") (pintype "passive"))
      (node (ref "C8") (pin "1") (pinfunction "1_1") (pintype "passive"))
      (node (ref "C9") (pin "1") (pinfunction "1_1") (pintype "passive"))
      (node (ref "D2") (pin "A") (pinfunction "A_A") (pintype "passive"))
      (node (ref "INVERT") (pin "P$3") (pinfunction "GND_P$3") (pintype "bidirectional"))
      (node (ref "JP10") (pin "3") (pinfunction "3_3") (pintype "passive"))
      (node (ref "JP3") (pin "2") (pinfunction "2_2") (pintype "passive"))
      (node (ref "JP7") (pin "3") (pinfunction "3_3") (pintype "passive"))
      (node (ref "JP9") (pin "3") (pinfunction "3_3") (pintype "passive"))
      (node (ref "OPA") (pin "P$2") (pinfunction "V-_P$2") (pintype "bidirectional"))
      (node (ref "R1") (pin "2") (pinfunction "2_2") (pintype "passive"))
      (node (ref "R10") (pin "2") (pinfunction "2_2") (pintype "passive"))
      (node (ref "R100") (pin "1") (pinfunction "1_1") (pintype "passive"))
      (node (ref "R14") (pin "2") (pinfunction "2_2") (pintype "passive"))
      (node (ref "R16") (pin "2") (pinfunction "2_2") (pintype "passive"))
      (node (ref "R18") (pin "2") (pinfunction "2_2") (pintype "passive"))
      (node (ref "R2") (pin "1") (pinfunction "1_1") (pintype "passive"))
      (node (ref "R20") (pin "2") (pinfunction "2_2") (pintype "passive"))
      (node (ref "R23") (pin "2") (pinfunction "2_2") (pintype "passive"))
      (node (ref "R24") (pin "2") (pinfunction "2_2") (pintype "passive"))
      (node (ref "R25") (pin "2") (pinfunction "2_2") (pintype "passive"))
      (node (ref "R26") (pin "2") (pinfunction "2_2") (pintype "passive"))
      (node (ref "R28") (pin "1") (pinfunction "1_1") (pintype "passive"))
      (node (ref "R3") (pin "1") (pinfunction "1_1") (pintype "passive"))
      (node (ref "R31") (pin "1") (pinfunction "1_1") (pintype "passive"))
      (node (ref "R33") (pin "1") (pinfunction "1_1") (pintype "passive"))
      (node (ref "R34") (pin "1") (pinfunction "1_1") (pintype "passive"))
      (node (ref "R4") (pin "2") (pinfunction "2_2") (pintype "passive"))
      (node (ref "R41") (pin "2") (pinfunction "2_2") (pintype "passive"))
      (node (ref "R67") (pin "1") (pinfunction "1_1") (pintype "passive"))
      (node (ref "R68") (pin "1") (pinfunction "1_1") (pintype "passive"))
      (node (ref "R7") (pin "2") (pinfunction "2_2") (pintype "passive"))
      (node (ref "R70") (pin "2") (pinfunction "2_2") (pintype "passive"))
      (node (ref "R8") (pin "2") (pinfunction "2_2") (pintype "passive"))
      (node (ref "R9") (pin "2") (pinfunction "2_2") (pintype "passive"))
      (node (ref "U$1") (pin "P$10") (pinfunction "HEAT_P$10") (pintype "bidirectional"))
      (node (ref "U$1") (pin "P$11") (pinfunction "HEAT_P$11") (pintype "bidirectional"))
      (node (ref "U$1") (pin "P$12") (pinfunction "HEAT_P$12") (pintype "bidirectional"))
      (node (ref "U$1") (pin "P$13") (pinfunction "HEAT_P$13") (pintype "bidirectional"))
      (node (ref "U$1") (pin "P$14") (pinfunction "HEAT_P$14") (pintype "bidirectional"))
      (node (ref "U$1") (pin "P$15") (pinfunction "HEAT_P$15") (pintype "bidirectional"))
      (node (ref "U$1") (pin "P$16") (pinfunction "HEAT_P$16") (pintype "bidirectional"))
      (node (ref "U$1") (pin "P$17") (pinfunction "HEAT_P$17") (pintype "bidirectional"))
      (node (ref "U$1") (pin "P$18") (pinfunction "HEAT_P$18") (pintype "bidirectional"))
      (node (ref "U$1") (pin "P$5") (pinfunction "GND_P$5") (pintype "bidirectional"))
      (node (ref "U$1") (pin "P$9") (pinfunction "HEAT_P$9") (pintype "bidirectional"))
      (node (ref "U$10") (pin "10") (pinfunction "SGND_10") (pintype "bidirectional"))
      (node (ref "U$10") (pin "HEAT") (pinfunction "HEAT_HEAT") (pintype "bidirectional"))
      (node (ref "U$10") (pin "P$1") (pinfunction "HEAT_P$1") (pintype "bidirectional"))
      (node (ref "U$10") (pin "P$10") (pinfunction "HEAT_P$10") (pintype "bidirectional"))
      (node (ref "U$10") (pin "P$11") (pinfunction "HEAT_P$11") (pintype "bidirectional"))
      (node (ref "U$10") (pin "P$12") (pinfunction "HEAT_P$12") (pintype "bidirectional"))
      (node (ref "U$10") (pin "P$13") (pinfunction "HEAT_P$13") (pintype "bidirectional"))
      (node (ref "U$10") (pin "P$14") (pinfunction "HEAT_P$14") (pintype "bidirectional"))
      (node (ref "U$10") (pin "P$15") (pinfunction "HEAT_P$15") (pintype "bidirectional"))
      (node (ref "U$10") (pin "P$2") (pinfunction "HEAT_P$2") (pintype "bidirectional"))
      (node (ref "U$10") (pin "P$3") (pinfunction "HEAT_P$3") (pintype "bidirectional"))
      (node (ref "U$10") (pin "P$4") (pinfunction "HEAT_P$4") (pintype "bidirectional"))
      (node (ref "U$10") (pin "P$5") (pinfunction "HEAT_P$5") (pintype "bidirectional"))
      (node (ref "U$10") (pin "P$6") (pinfunction "HEAT_P$6") (pintype "bidirectional"))
      (node (ref "U$10") (pin "P$7") (pinfunction "HEAT_P$7") (pintype "bidirectional"))
      (node (ref "U$10") (pin "P$8") (pinfunction "HEAT_P$8") (pintype "bidirectional"))
      (node (ref "U$10") (pin "P$9") (pinfunction "HEAT_P$9") (pintype "bidirectional"))
      (node (ref "U$23") (pin "14") (pinfunction "SGND_14") (pintype "bidirectional"))
      (node (ref "U$23") (pin "20") (pinfunction "PGND_20") (pintype "bidirectional"))
      (node (ref "U$23") (pin "25") (pinfunction "PGND_25") (pintype "bidirectional"))
      (node (ref "U$23") (pin "28") (pinfunction "PWM_28") (pintype "bidirectional"))
      (node (ref "U$23") (pin "29") (pinfunction "PGND_29") (pintype "bidirectional"))
      (node (ref "U$23") (pin "4") (pinfunction "PGND_4") (pintype "bidirectional"))
      (node (ref "U$23") (pin "9") (pinfunction "PGND_9") (pintype "bidirectional"))
      (node (ref "U$23") (pin "P$1") (pinfunction "PGND_P$1") (pintype "bidirectional"))
      (node (ref "U$23") (pin "P$10") (pinfunction "PGND_P$10") (pintype "bidirectional"))
      (node (ref "U$23") (pin "P$2") (pinfunction "PGND_P$2") (pintype "bidirectional"))
      (node (ref "U$23") (pin "P$3") (pinfunction "PGND_P$3") (pintype "bidirectional"))
      (node (ref "U$23") (pin "P$4") (pinfunction "PGND_P$4") (pintype "bidirectional"))
      (node (ref "U$23") (pin "P$5") (pinfunction "PGND_P$5") (pintype "bidirectional"))
      (node (ref "U$23") (pin "P$6") (pinfunction "PGND_P$6") (pintype "bidirectional"))
      (node (ref "U$23") (pin "P$7") (pinfunction "PGND_P$7") (pintype "bidirectional"))
      (node (ref "U$23") (pin "P$8") (pinfunction "PGND_P$8") (pintype "bidirectional"))
      (node (ref "U$23") (pin "P$9") (pinfunction "PGND_P$9") (pintype "bidirectional"))
      (node (ref "U$25") (pin "P$1") (pinfunction "CCW_P$1") (pintype "bidirectional"))
      (node (ref "U$3") (pin "P$1") (pinfunction "AGND_P$1") (pintype "bidirectional"))
      (node (ref "U$3") (pin "P$4") (pinfunction "GND_P$4") (pintype "bidirectional"))
      (node (ref "U$5") (pin "10") (pinfunction "SGND_10") (pintype "bidirectional"))
      (node (ref "U$5") (pin "HEAT") (pinfunction "HEAT_HEAT") (pintype "bidirectional"))
      (node (ref "U$5") (pin "P$1") (pinfunction "HEAT_P$1") (pintype "bidirectional"))
      (node (ref "U$5") (pin "P$10") (pinfunction "HEAT_P$10") (pintype "bidirectional"))
      (node (ref "U$5") (pin "P$11") (pinfunction "HEAT_P$11") (pintype "bidirectional"))
      (node (ref "U$5") (pin "P$12") (pinfunction "HEAT_P$12") (pintype "bidirectional"))
      (node (ref "U$5") (pin "P$13") (pinfunction "HEAT_P$13") (pintype "bidirectional"))
      (node (ref "U$5") (pin "P$14") (pinfunction "HEAT_P$14") (pintype "bidirectional"))
      (node (ref "U$5") (pin "P$15") (pinfunction "HEAT_P$15") (pintype "bidirectional"))
      (node (ref "U$5") (pin "P$2") (pinfunction "HEAT_P$2") (pintype "bidirectional"))
      (node (ref "U$5") (pin "P$3") (pinfunction "HEAT_P$3") (pintype "bidirectional"))
      (node (ref "U$5") (pin "P$4") (pinfunction "HEAT_P$4") (pintype "bidirectional"))
      (node (ref "U$5") (pin "P$5") (pinfunction "HEAT_P$5") (pintype "bidirectional"))
      (node (ref "U$5") (pin "P$6") (pinfunction "HEAT_P$6") (pintype "bidirectional"))
      (node (ref "U$5") (pin "P$7") (pinfunction "HEAT_P$7") (pintype "bidirectional"))
      (node (ref "U$5") (pin "P$8") (pinfunction "HEAT_P$8") (pintype "bidirectional"))
      (node (ref "U$5") (pin "P$9") (pinfunction "HEAT_P$9") (pintype "bidirectional"))
      (node (ref "U$59") (pin "14") (pinfunction "SGND_14") (pintype "bidirectional"))
      (node (ref "U$59") (pin "20") (pinfunction "PGND_20") (pintype "bidirectional"))
      (node (ref "U$59") (pin "25") (pinfunction "PGND_25") (pintype "bidirectional"))
      (node (ref "U$59") (pin "28") (pinfunction "PWM_28") (pintype "bidirectional"))
      (node (ref "U$59") (pin "29") (pinfunction "PGND_29") (pintype "bidirectional"))
      (node (ref "U$59") (pin "4") (pinfunction "PGND_4") (pintype "bidirectional"))
      (node (ref "U$59") (pin "9") (pinfunction "PGND_9") (pintype "bidirectional"))
      (node (ref "U$59") (pin "P$1") (pinfunction "PGND_P$1") (pintype "bidirectional"))
      (node (ref "U$59") (pin "P$10") (pinfunction "PGND_P$10") (pintype "bidirectional"))
      (node (ref "U$59") (pin "P$2") (pinfunction "PGND_P$2") (pintype "bidirectional"))
      (node (ref "U$59") (pin "P$3") (pinfunction "PGND_P$3") (pintype "bidirectional"))
      (node (ref "U$59") (pin "P$4") (pinfunction "PGND_P$4") (pintype "bidirectional"))
      (node (ref "U$59") (pin "P$5") (pinfunction "PGND_P$5") (pintype "bidirectional"))
      (node (ref "U$59") (pin "P$6") (pinfunction "PGND_P$6") (pintype "bidirectional"))
      (node (ref "U$59") (pin "P$7") (pinfunction "PGND_P$7") (pintype "bidirectional"))
      (node (ref "U$59") (pin "P$8") (pinfunction "PGND_P$8") (pintype "bidirectional"))
      (node (ref "U$59") (pin "P$9") (pinfunction "PGND_P$9") (pintype "bidirectional"))
    )
    (net (code "10") (name "/INA_BMS+") (class "Default")
      (node (ref "C47") (pin "P$1") (pinfunction "1_P$1") (pintype "passive"))
      (node (ref "C55") (pin "P$1") (pinfunction "1_P$1") (pintype "passive"))
      (node (ref "R72") (pin "2") (pinfunction "2_2") (pintype "passive"))
      (node (ref "U$23") (pin "19") (pinfunction "VIN_19") (pintype "bidirectional"))
      (node (ref "U$23") (pin "22") (pinfunction "PVIN_22") (pintype "bidirectional"))
      (node (ref "U$23") (pin "23") (pinfunction "PVIN_23") (pintype "bidirectional"))
      (node (ref "U$59") (pin "6") (pinfunction "PVOUT_6") (pintype "bidirectional"))
      (node (ref "U$59") (pin "7") (pinfunction "PVOUT_7") (pintype "bidirectional"))
    )
    (net (code "11") (name "/INA_BUS+") (class "Default")
      (node (ref "C48") (pin "P$1") (pinfunction "1_P$1") (pintype "passive"))
      (node (ref "C54") (pin "P$1") (pinfunction "1_P$1") (pintype "passive"))
      (node (ref "R40") (pin "1") (pinfunction "1_1") (pintype "passive"))
      (node (ref "R65") (pin "2") (pinfunction "2_2") (pintype "passive"))
      (node (ref "U$23") (pin "6") (pinfunction "PVOUT_6") (pintype "bidirectional"))
      (node (ref "U$23") (pin "7") (pinfunction "PVOUT_7") (pintype "bidirectional"))
      (node (ref "U$25") (pin "P$3") (pinfunction "CW_P$3") (pintype "bidirectional"))
      (node (ref "U$59") (pin "19") (pinfunction "VIN_19") (pintype "bidirectional"))
      (node (ref "U$59") (pin "22") (pinfunction "PVIN_22") (pintype "bidirectional"))
      (node (ref "U$59") (pin "23") (pinfunction "PVIN_23") (pintype "bidirectional"))
    )
    (net (code "12") (name "/INTVCC") (class "Default")
      (node (ref "C22") (pin "2") (pinfunction "2_2") (pintype "passive"))
      (node (ref "C23") (pin "2") (pinfunction "2_2") (pintype "passive"))
      (node (ref "JP1") (pin "2") (pinfunction "2_2") (pintype "passive"))
      (node (ref "JP10") (pin "1") (pinfunction "1_1") (pintype "passive"))
      (node (ref "JP4") (pin "3") (pinfunction "3_3") (pintype "passive"))
      (node (ref "JP5") (pin "3") (pinfunction "3_3") (pintype "passive"))
      (node (ref "JP6") (pin "3") (pinfunction "3_3") (pintype "passive"))
      (node (ref "R21") (pin "2") (pinfunction "2_2") (pintype "passive"))
      (node (ref "R22") (pin "2") (pinfunction "2_2") (pintype "passive"))
      (node (ref "U$5") (pin "22") (pinfunction "INTVCC_22") (pintype "bidirectional"))
    )
    (net (code "13") (name "/PGOOD1") (class "Default")
      (node (ref "LED_R1") (pin "C") (pinfunction "C_C") (pintype "passive"))
      (node (ref "U$59") (pin "10") (pinfunction "PGOOD_10") (pintype "bidirectional"))
    )
    (net (code "14") (name "/PGOOD2") (class "Default")
      (node (ref "LED_R2") (pin "C") (pinfunction "C_C") (pintype "passive"))
      (node (ref "U$23") (pin "10") (pinfunction "PGOOD_10") (pintype "bidirectional"))
    )
    (net (code "15") (name "/RUN") (class "Default")
      (node (ref "R38") (pin "2") (pinfunction "2_2") (pintype "passive"))
      (node (ref "R40") (pin "2") (pinfunction "2_2") (pintype "passive"))
      (node (ref "R41") (pin "1") (pinfunction "1_1") (pintype "passive"))
    )
    (net (code "16") (name "/VDD") (class "Default")
      (node (ref "C6") (pin "1") (pinfunction "1_1") (pintype "passive"))
      (node (ref "R13") (pin "2") (pinfunction "2_2") (pintype "passive"))
      (node (ref "U$10") (pin "28") (pinfunction "VON1_28") (pintype "bidirectional"))
      (node (ref "U$11") (pin "P$2") (pinfunction "2_P$2") (pintype "passive"))
    )
    (net (code "17") (name "/VIN") (class "Default")
      (node (ref "C38") (pin "2") (pinfunction "2_2") (pintype "passive"))
      (node (ref "C39") (pin "2") (pinfunction "2_2") (pintype "passive"))
      (node (ref "JP7") (pin "1") (pinfunction "1_1") (pintype "passive"))
      (node (ref "JP9") (pin "1") (pinfunction "1_1") (pintype "passive"))
      (node (ref "U$5") (pin "18") (pinfunction "VIN2_18") (pintype "bidirectional"))
      (node (ref "U$5") (pin "19") (pinfunction "_VIN2_19") (pintype "bidirectional"))
      (node (ref "U$5") (pin "24") (pinfunction "VIN1_24") (pintype "bidirectional"))
      (node (ref "U$5") (pin "25") (pinfunction "_VIN1_25") (pintype "bidirectional"))
    )
    (net (code "18") (name "/VON1") (class "Default")
      (node (ref "C28") (pin "2") (pinfunction "2_2") (pintype "passive"))
      (node (ref "C31") (pin "2") (pinfunction "2_2") (pintype "passive"))
      (node (ref "C32") (pin "2") (pinfunction "2_2") (pintype "passive"))
      (node (ref "C34") (pin "2") (pinfunction "2_2") (pintype "passive"))
      (node (ref "R29") (pin "1") (pinfunction "1_1") (pintype "passive"))
      (node (ref "U$5") (pin "28") (pinfunction "VON1_28") (pintype "bidirectional"))
      (node (ref "U$7") (pin "P$1") (pinfunction "1_P$1") (pintype "passive"))
    )
    (net (code "19") (name "/VON2") (class "Default")
      (node (ref "C27") (pin "2") (pinfunction "2_2") (pintype "passive"))
      (node (ref "C29") (pin "2") (pinfunction "2_2") (pintype "passive"))
      (node (ref "C30") (pin "2") (pinfunction "2_2") (pintype "passive"))
      (node (ref "C33") (pin "2") (pinfunction "2_2") (pintype "passive"))
      (node (ref "R27") (pin "1") (pinfunction "1_1") (pintype "passive"))
      (node (ref "U$5") (pin "15") (pinfunction "VON2_15") (pintype "bidirectional"))
      (node (ref "U$6") (pin "P$1") (pinfunction "1_P$1") (pintype "passive"))
    )
    (net (code "20") (name "/Y") (class "Default")
      (node (ref "INVERT") (pin "P$4") (pinfunction "Y_P$4") (pintype "bidirectional"))
      (node (ref "R57") (pin "1") (pinfunction "1_1") (pintype "passive"))
      (node (ref "U$23") (pin "18") (pinfunction "RUN_18") (pintype "bidirectional"))
    )
    (net (code "21") (name "Net-(3,3µH-Pad1)") (class "Default")
      (node (ref "3,3µH") (pin "1") (pinfunction "1_1") (pintype "bidirectional"))
      (node (ref "C41") (pin "1") (pinfunction "1_1") (pintype "passive"))
      (node (ref "U$59") (pin "5") (pinfunction "SW2_5") (pintype "bidirectional"))
      (node (ref "U$59") (pin "8") (pinfunction "SW2_8") (pintype "bidirectional"))
    )
    (net (code "22") (name "Net-(3,3µH-Pad2)") (class "Default")
      (node (ref "3,3µH") (pin "2") (pinfunction "2_2") (pintype "bidirectional"))
      (node (ref "C40") (pin "1") (pinfunction "1_1") (pintype "passive"))
      (node (ref "U$59") (pin "21") (pinfunction "SW1_21") (pintype "bidirectional"))
      (node (ref "U$59") (pin "24") (pinfunction "SW1_24") (pintype "bidirectional"))
    )
    (net (code "23") (name "Net-(3,3µH1-Pad1)") (class "Default")
      (node (ref "3,3µH1") (pin "1") (pinfunction "1_1") (pintype "bidirectional"))
      (node (ref "C50") (pin "1") (pinfunction "1_1") (pintype "passive"))
      (node (ref "U$23") (pin "5") (pinfunction "SW2_5") (pintype "bidirectional"))
      (node (ref "U$23") (pin "8") (pinfunction "SW2_8") (pintype "bidirectional"))
    )
    (net (code "24") (name "Net-(3,3µH1-Pad2)") (class "Default")
      (node (ref "3,3µH1") (pin "2") (pinfunction "2_2") (pintype "bidirectional"))
      (node (ref "C49") (pin "1") (pinfunction "1_1") (pintype "passive"))
      (node (ref "U$23") (pin "21") (pinfunction "SW1_21") (pintype "bidirectional"))
      (node (ref "U$23") (pin "24") (pinfunction "SW1_24") (pintype "bidirectional"))
    )
    (net (code "25") (name "Net-(C18-Pad2)") (class "Default")
      (node (ref "C18") (pin "2") (pinfunction "2_2") (pintype "passive"))
      (node (ref "R17") (pin "1") (pinfunction "1_1") (pintype "passive"))
    )
    (net (code "26") (name "Net-(C19-Pad2)") (class "Default")
      (node (ref "C19") (pin "2") (pinfunction "2_2") (pintype "passive"))
      (node (ref "R19") (pin "1") (pinfunction "1_1") (pintype "passive"))
    )
    (net (code "27") (name "Net-(C21-Pad2)") (class "Default")
      (node (ref "C21") (pin "2") (pinfunction "2_2") (pintype "passive"))
      (node (ref "JP8") (pin "1") (pinfunction "1_1") (pintype "passive"))
    )
    (net (code "28") (name "Net-(C24-Pad2)") (class "Default")
      (node (ref "C24") (pin "2") (pinfunction "2_2") (pintype "passive"))
      (node (ref "JP11") (pin "1") (pinfunction "1_1") (pintype "passive"))
    )
    (net (code "29") (name "Net-(C36-Pad1)") (class "Default")
      (node (ref "C36") (pin "1") (pinfunction "1_1") (pintype "passive"))
      (node (ref "R10") (pin "1") (pinfunction "1_1") (pintype "passive"))
    )
    (net (code "30") (name "Net-(C44-Pad1)") (class "Default")
      (node (ref "C44") (pin "1") (pinfunction "1_1") (pintype "passive"))
      (node (ref "R69") (pin "2") (pinfunction "2_2") (pintype "passive"))
    )
    (net (code "31") (name "Net-(C46-Pad1)") (class "Default")
      (node (ref "C46") (pin "1") (pinfunction "1_1") (pintype "passive"))
      (node (ref "R66") (pin "1") (pinfunction "1_1") (pintype "passive"))
    )
    (net (code "32") (name "Net-(C52-Pad1)") (class "Default")
      (node (ref "C52") (pin "1") (pinfunction "1_1") (pintype "passive"))
      (node (ref "R30") (pin "2") (pinfunction "2_2") (pintype "passive"))
    )
    (net (code "33") (name "Net-(JP2-Pad2)") (class "Default")
      (node (ref "JP2") (pin "2") (pinfunction "2_2") (pintype "passive"))
      (node (ref "R16") (pin "1") (pinfunction "1_1") (pintype "passive"))
    )
    (net (code "34") (name "Net-(JP11-Pad3)") (class "Default")
      (node (ref "JP11") (pin "3") (pinfunction "3_3") (pintype "passive"))
      (node (ref "JP12") (pin "1") (pinfunction "1_1") (pintype "passive"))
    )
    (net (code "35") (name "Net-(JP13-Pad1)") (class "Default")
      (node (ref "JP13") (pin "1") (pinfunction "1_1") (pintype "passive"))
      (node (ref "JP8") (pin "3") (pinfunction "3_3") (pintype "passive"))
    )
    (net (code "36") (name "Net-(JP14-Pad1)") (class "Default")
      (node (ref "JP14") (pin "1") (pinfunction "1_1") (pintype "passive"))
      (node (ref "U$14") (pin "P$1") (pinfunction "P$1_P$1") (pintype "bidirectional"))
    )
    (net (code "37") (name "Net-(JP15-Pad1)") (class "Default")
      (node (ref "JP15") (pin "1") (pinfunction "1_1") (pintype "passive"))
      (node (ref "U$15") (pin "P$1") (pinfunction "P$1_P$1") (pintype "bidirectional"))
    )
    (net (code "38") (name "Net-(JP16-Pad1)") (class "Default")
      (node (ref "JP16") (pin "1") (pinfunction "1_1") (pintype "passive"))
      (node (ref "U$16") (pin "P$1") (pinfunction "P$1_P$1") (pintype "bidirectional"))
    )
    (net (code "39") (name "Net-(JP17-Pad1)") (class "Default")
      (node (ref "JP17") (pin "1") (pinfunction "1_1") (pintype "passive"))
      (node (ref "U$14") (pin "P$2") (pinfunction "P$2_P$2") (pintype "bidirectional"))
    )
    (net (code "40") (name "Net-(JP18-Pad1)") (class "Default")
      (node (ref "JP18") (pin "1") (pinfunction "1_1") (pintype "passive"))
      (node (ref "U$15") (pin "P$2") (pinfunction "P$2_P$2") (pintype "bidirectional"))
    )
    (net (code "41") (name "Net-(JP19-Pad1)") (class "Default")
      (node (ref "JP19") (pin "1") (pinfunction "1_1") (pintype "passive"))
      (node (ref "U$16") (pin "P$2") (pinfunction "P$2_P$2") (pintype "bidirectional"))
    )
    (net (code "42") (name "Net-(JP20-Pad1)") (class "Default")
      (node (ref "JP20") (pin "1") (pinfunction "1_1") (pintype "passive"))
      (node (ref "U$17") (pin "P$1") (pinfunction "P$1_P$1") (pintype "bidirectional"))
    )
    (net (code "43") (name "Net-(JP21-Pad1)") (class "Default")
      (node (ref "JP21") (pin "1") (pinfunction "1_1") (pintype "passive"))
      (node (ref "U$18") (pin "P$1") (pinfunction "P$1_P$1") (pintype "bidirectional"))
    )
    (net (code "44") (name "Net-(JP22-Pad1)") (class "Default")
      (node (ref "JP22") (pin "1") (pinfunction "1_1") (pintype "passive"))
      (node (ref "U$19") (pin "P$1") (pinfunction "P$1_P$1") (pintype "bidirectional"))
    )
    (net (code "45") (name "Net-(JP23-Pad1)") (class "Default")
      (node (ref "JP23") (pin "1") (pinfunction "1_1") (pintype "passive"))
      (node (ref "U$17") (pin "P$2") (pinfunction "P$2_P$2") (pintype "bidirectional"))
    )
    (net (code "46") (name "Net-(JP24-Pad1)") (class "Default")
      (node (ref "JP24") (pin "1") (pinfunction "1_1") (pintype "passive"))
      (node (ref "U$18") (pin "P$2") (pinfunction "P$2_P$2") (pintype "bidirectional"))
    )
    (net (code "47") (name "Net-(JP25-Pad1)") (class "Default")
      (node (ref "JP25") (pin "1") (pinfunction "1_1") (pintype "passive"))
      (node (ref "U$19") (pin "P$2") (pinfunction "P$2_P$2") (pintype "bidirectional"))
    )
    (net (code "48") (name "Net-(JP26-Pad1)") (class "Default")
      (node (ref "JP26") (pin "1") (pinfunction "1_1") (pintype "passive"))
      (node (ref "U$20") (pin "P$1") (pinfunction "P$1_P$1") (pintype "bidirectional"))
    )
    (net (code "49") (name "Net-(JP27-Pad1)") (class "Default")
      (node (ref "JP27") (pin "1") (pinfunction "1_1") (pintype "passive"))
      (node (ref "U$21") (pin "P$1") (pinfunction "P$1_P$1") (pintype "bidirectional"))
    )
    (net (code "50") (name "Net-(JP28-Pad1)") (class "Default")
      (node (ref "JP28") (pin "1") (pinfunction "1_1") (pintype "passive"))
      (node (ref "U$22") (pin "P$1") (pinfunction "P$1_P$1") (pintype "bidirectional"))
    )
    (net (code "51") (name "Net-(JP29-Pad1)") (class "Default")
      (node (ref "JP29") (pin "1") (pinfunction "1_1") (pintype "passive"))
      (node (ref "U$20") (pin "P$2") (pinfunction "P$2_P$2") (pintype "bidirectional"))
    )
    (net (code "52") (name "Net-(JP30-Pad1)") (class "Default")
      (node (ref "JP30") (pin "1") (pinfunction "1_1") (pintype "passive"))
      (node (ref "U$21") (pin "P$2") (pinfunction "P$2_P$2") (pintype "bidirectional"))
    )
    (net (code "53") (name "Net-(JP31-Pad1)") (class "Default")
      (node (ref "JP31") (pin "1") (pinfunction "1_1") (pintype "passive"))
      (node (ref "U$22") (pin "P$2") (pinfunction "P$2_P$2") (pintype "bidirectional"))
    )
    (net (code "54") (name "Net-(JP32-Pad1)") (class "Default")
      (node (ref "JP32") (pin "1") (pinfunction "1_1") (pintype "passive"))
      (node (ref "U$8") (pin "P$1") (pinfunction "P$1_P$1") (pintype "bidirectional"))
    )
    (net (code "55") (name "Net-(JP33-Pad1)") (class "Default")
      (node (ref "JP33") (pin "1") (pinfunction "1_1") (pintype "passive"))
      (node (ref "U$9") (pin "P$1") (pinfunction "P$1_P$1") (pintype "bidirectional"))
    )
    (net (code "56") (name "Net-(JP34-Pad1)") (class "Default")
      (node (ref "JP34") (pin "1") (pinfunction "1_1") (pintype "passive"))
      (node (ref "U$13") (pin "P$1") (pinfunction "P$1_P$1") (pintype "bidirectional"))
    )
    (net (code "57") (name "Net-(JP35-Pad1)") (class "Default")
      (node (ref "JP35") (pin "1") (pinfunction "1_1") (pintype "passive"))
      (node (ref "U$8") (pin "P$2") (pinfunction "P$2_P$2") (pintype "bidirectional"))
    )
    (net (code "58") (name "Net-(JP36-Pad1)") (class "Default")
      (node (ref "JP36") (pin "1") (pinfunction "1_1") (pintype "passive"))
      (node (ref "U$9") (pin "P$2") (pinfunction "P$2_P$2") (pintype "bidirectional"))
    )
    (net (code "59") (name "Net-(JP37-Pad1)") (class "Default")
      (node (ref "JP37") (pin "1") (pinfunction "1_1") (pintype "passive"))
      (node (ref "U$13") (pin "P$2") (pinfunction "P$2_P$2") (pintype "bidirectional"))
    )
    (net (code "60") (name "Net-(LED1-PadC)") (class "Default")
      (node (ref "LED1") (pin "C") (pinfunction "C_C") (pintype "passive"))
      (node (ref "R31") (pin "2") (pinfunction "2_2") (pintype "passive"))
    )
    (net (code "61") (name "Net-(LED2-PadC)") (class "Default")
      (node (ref "LED2") (pin "C") (pinfunction "C_C") (pintype "passive"))
      (node (ref "R2") (pin "2") (pinfunction "2_2") (pintype "passive"))
    )
    (net (code "62") (name "Net-(LED_G1-PadC)") (class "Default")
      (node (ref "LED_G1") (pin "C") (pinfunction "C_C") (pintype "passive"))
      (node (ref "R100") (pin "2") (pinfunction "2_2") (pintype "passive"))
    )
    (net (code "63") (name "Net-(LED_G2-PadC)") (class "Default")
      (node (ref "LED_G2") (pin "C") (pinfunction "C_C") (pintype "passive"))
      (node (ref "R33") (pin "2") (pinfunction "2_2") (pintype "passive"))
    )
    (net (code "64") (name "Net-(LED_R1-PadA)") (class "Default")
      (node (ref "LED_R1") (pin "A") (pinfunction "A_A") (pintype "passive"))
      (node (ref "R32") (pin "2") (pinfunction "2_2") (pintype "passive"))
    )
    (net (code "65") (name "Net-(LED_R2-PadA)") (class "Default")
      (node (ref "LED_R2") (pin "A") (pinfunction "A_A") (pintype "passive"))
      (node (ref "R57") (pin "2") (pinfunction "2_2") (pintype "passive"))
    )
    (net (code "66") (name "Net-(OPA-IN+)") (class "Default")
      (node (ref "OPA") (pin "P$3") (pinfunction "IN+_P$3") (pintype "bidirectional"))
      (node (ref "R38") (pin "1") (pinfunction "1_1") (pintype "passive"))
      (node (ref "R39") (pin "1") (pinfunction "1_1") (pintype "passive"))
    )
    (net (code "67") (name "Net-(OPA-IN-)") (class "Default")
      (node (ref "OPA") (pin "P$4") (pinfunction "IN-_P$4") (pintype "bidirectional"))
      (node (ref "R36") (pin "1") (pinfunction "1_1") (pintype "passive"))
      (node (ref "R37") (pin "1") (pinfunction "1_1") (pintype "passive"))
    )
    (net (code "68") (name "Net-(U$1-BST)") (class "Default")
      (node (ref "C2") (pin "2") (pinfunction "2_2") (pintype "passive"))
      (node (ref "U$1") (pin "P$8") (pinfunction "BST_P$8") (pintype "bidirectional"))
    )
    (net (code "69") (name "Net-(U$1-COMP)") (class "Default")
      (node (ref "C36") (pin "2") (pinfunction "2_2") (pintype "passive"))
      (node (ref "U$1") (pin "P$3") (pinfunction "COMP_P$3") (pintype "bidirectional"))
    )
    (net (code "70") (name "Net-(U$1-EN)") (class "Default")
      (node (ref "R6") (pin "1") (pinfunction "1_1") (pintype "passive"))
      (node (ref "R7") (pin "1") (pinfunction "1_1") (pintype "passive"))
      (node (ref "U$1") (pin "P$2") (pinfunction "EN_P$2") (pintype "bidirectional"))
    )
    (net (code "71") (name "Net-(U$1-FB)") (class "Default")
      (node (ref "R4") (pin "1") (pinfunction "1_1") (pintype "passive"))
      (node (ref "R5") (pin "2") (pinfunction "2_2") (pintype "passive"))
      (node (ref "U$1") (pin "P$4") (pinfunction "FB_P$4") (pintype "bidirectional"))
    )
    (net (code "72") (name "Net-(U$1-FREQ)") (class "Default")
      (node (ref "R3") (pin "2") (pinfunction "2_2") (pintype "passive"))
      (node (ref "U$1") (pin "P$6") (pinfunction "FREQ_P$6") (pintype "bidirectional"))
    )
    (net (code "73") (name "Net-(U$1-SW)") (class "Default")
      (node (ref "C2") (pin "1") (pinfunction "1_1") (pintype "passive"))
      (node (ref "D2") (pin "C") (pinfunction "C_C") (pintype "passive"))
      (node (ref "U$1") (pin "P$1") (pinfunction "SW_P$1") (pintype "bidirectional"))
      (node (ref "U$2") (pin "P$2") (pinfunction "2_P$2") (pintype "passive"))
    )
    (net (code "74") (name "Net-(U$1-VIN)") (class "Default")
      (node (ref "C4") (pin "2") (pinfunction "2_2") (pintype "passive"))
      (node (ref "R6") (pin "2") (pinfunction "2_2") (pintype "passive"))
      (node (ref "U$1") (pin "P$7") (pinfunction "VIN_P$7") (pintype "bidirectional"))
    )
    (net (code "75") (name "Net-(U$3-BST)") (class "Default")
      (node (ref "C7") (pin "2") (pinfunction "2_2") (pintype "passive"))
      (node (ref "U$3") (pin "P$5") (pinfunction "BST_P$5") (pintype "bidirectional"))
    )
    (net (code "76") (name "Net-(U$3-EN)") (class "Default")
      (node (ref "R11") (pin "2") (pinfunction "2_2") (pintype "passive"))
      (node (ref "U$3") (pin "P$6") (pinfunction "EN_P$6") (pintype "bidirectional"))
    )
    (net (code "77") (name "Net-(U$3-FB)") (class "Default")
      (node (ref "C11") (pin "2") (pinfunction "2_2") (pintype "passive"))
      (node (ref "R14") (pin "1") (pinfunction "1_1") (pintype "passive"))
      (node (ref "R15") (pin "1") (pinfunction "1_1") (pintype "passive"))
      (node (ref "U$3") (pin "P$8") (pinfunction "FB_P$8") (pintype "bidirectional"))
    )
    (net (code "78") (name "Net-(U$3-IN)") (class "Default")
      (node (ref "C10") (pin "2") (pinfunction "2_2") (pintype "passive"))
      (node (ref "C9") (pin "2") (pinfunction "2_2") (pintype "passive"))
      (node (ref "R11") (pin "1") (pinfunction "1_1") (pintype "passive"))
      (node (ref "U$3") (pin "P$2") (pinfunction "IN_P$2") (pintype "bidirectional"))
    )
    (net (code "79") (name "Net-(U$3-SW)") (class "Default")
      (node (ref "C7") (pin "1") (pinfunction "1_1") (pintype "passive"))
      (node (ref "U$3") (pin "P$3") (pinfunction "SW_P$3") (pintype "bidirectional"))
      (node (ref "U$4") (pin "P$2") (pinfunction "2_P$2") (pintype "passive"))
    )
    (net (code "80") (name "Net-(U$3-VCC)") (class "Default")
      (node (ref "C8") (pin "2") (pinfunction "2_2") (pintype "passive"))
      (node (ref "U$3") (pin "P$7") (pinfunction "VCC_P$7") (pintype "bidirectional"))
    )
    (net (code "81") (name "Net-(U$4-1)") (class "Default")
      (node (ref "C11") (pin "1") (pinfunction "1_1") (pintype "passive"))
      (node (ref "C12") (pin "2") (pinfunction "2_2") (pintype "passive"))
      (node (ref "C13") (pin "2") (pinfunction "2_2") (pintype "passive"))
      (node (ref "R15") (pin "2") (pinfunction "2_2") (pintype "passive"))
      (node (ref "U$4") (pin "P$1") (pinfunction "1_P$1") (pintype "passive"))
    )
    (net (code "82") (name "Net-(U$5-BOOST1)") (class "Default")
      (node (ref "C26") (pin "2") (pinfunction "2_2") (pintype "passive"))
      (node (ref "U$5") (pin "23") (pinfunction "BOOST1_23") (pintype "bidirectional"))
    )
    (net (code "83") (name "Net-(U$5-BOOST2)") (class "Default")
      (node (ref "C25") (pin "2") (pinfunction "2_2") (pintype "passive"))
      (node (ref "U$5") (pin "20") (pinfunction "BOOST2_20") (pintype "bidirectional"))
    )
    (net (code "84") (name "Net-(U$5-ITH1)") (class "Default")
      (node (ref "JP6") (pin "1") (pinfunction "1_1") (pintype "passive"))
      (node (ref "JP6") (pin "2") (pinfunction "2_2") (pintype "passive"))
      (node (ref "R19") (pin "2") (pinfunction "2_2") (pintype "passive"))
      (node (ref "U$5") (pin "1") (pinfunction "ITH1_1") (pintype "bidirectional"))
    )
    (net (code "85") (name "Net-(U$5-ITH2)") (class "Default")
      (node (ref "JP4") (pin "1") (pinfunction "1_1") (pintype "passive"))
      (node (ref "JP4") (pin "2") (pinfunction "2_2") (pintype "passive"))
      (node (ref "R17") (pin "2") (pinfunction "2_2") (pintype "passive"))
      (node (ref "U$5") (pin "14") (pinfunction "ITH2_14") (pintype "bidirectional"))
    )
    (net (code "86") (name "Net-(U$5-MODE)") (class "Default")
      (node (ref "JP1") (pin "1") (pinfunction "1_1") (pintype "passive"))
      (node (ref "JP2") (pin "1") (pinfunction "1_1") (pintype "passive"))
      (node (ref "JP3") (pin "1") (pinfunction "1_1") (pintype "passive"))
      (node (ref "U$5") (pin "7") (pinfunction "MODE_7") (pintype "bidirectional"))
    )
    (net (code "87") (name "Net-(U$5-PGOOD1)") (class "Default")
      (node (ref "R22") (pin "1") (pinfunction "1_1") (pintype "passive"))
      (node (ref "U$5") (pin "4") (pinfunction "PGOOD1_4") (pintype "bidirectional"))
    )
    (net (code "88") (name "Net-(U$5-PGOOD2)") (class "Default")
      (node (ref "R21") (pin "1") (pinfunction "1_1") (pintype "passive"))
      (node (ref "U$5") (pin "11") (pinfunction "PGOOD2_11") (pintype "bidirectional"))
    )
    (net (code "89") (name "Net-(U$5-PHMODE)") (class "Default")
      (node (ref "JP10") (pin "2") (pinfunction "2_2") (pintype "passive"))
      (node (ref "R24") (pin "1") (pinfunction "1_1") (pintype "passive"))
      (node (ref "U$5") (pin "5") (pinfunction "PHMODE_5") (pintype "bidirectional"))
    )
    (net (code "90") (name "Net-(U$5-RT)") (class "Default")
      (node (ref "JP5") (pin "1") (pinfunction "1_1") (pintype "passive"))
      (node (ref "JP5") (pin "2") (pinfunction "2_2") (pintype "passive"))
      (node (ref "R18") (pin "1") (pinfunction "1_1") (pintype "passive"))
      (node (ref "U$5") (pin "8") (pinfunction "RT_8") (pintype "bidirectional"))
    )
    (net (code "91") (name "Net-(U$5-RUN1)") (class "Default")
      (node (ref "JP9") (pin "2") (pinfunction "2_2") (pintype "passive"))
      (node (ref "R23") (pin "1") (pinfunction "1_1") (pintype "passive"))
      (node (ref "U$5") (pin "6") (pinfunction "RUN1_6") (pintype "bidirectional"))
    )
    (net (code "92") (name "Net-(U$5-RUN2)") (class "Default")
      (node (ref "JP7") (pin "2") (pinfunction "2_2") (pintype "passive"))
      (node (ref "R20") (pin "1") (pinfunction "1_1") (pintype "passive"))
      (node (ref "U$5") (pin "9") (pinfunction "RUN2_9") (pintype "bidirectional"))
    )
    (net (code "93") (name "Net-(U$5-SS1)") (class "Default")
      (node (ref "JP11") (pin "2") (pinfunction "2_2") (pintype "passive"))
      (node (ref "U$5") (pin "2") (pinfunction "SS1_2") (pintype "bidirectional"))
    )
    (net (code "94") (name "Net-(U$5-SS2)") (class "Default")
      (node (ref "JP8") (pin "2") (pinfunction "2_2") (pintype "passive"))
      (node (ref "U$5") (pin "13") (pinfunction "SS2_13") (pintype "bidirectional"))
    )
    (net (code "95") (name "Net-(U$5-SW1)") (class "Default")
      (node (ref "C26") (pin "1") (pinfunction "1_1") (pintype "passive"))
      (node (ref "U$5") (pin "26") (pinfunction "SW1_26") (pintype "bidirectional"))
      (node (ref "U$5") (pin "27") (pinfunction "_SW1_27") (pintype "bidirectional"))
      (node (ref "U$7") (pin "P$2") (pinfunction "2_P$2") (pintype "passive"))
    )
    (net (code "96") (name "Net-(U$5-SW2)") (class "Default")
      (node (ref "C25") (pin "1") (pinfunction "1_1") (pintype "passive"))
      (node (ref "U$5") (pin "16") (pinfunction "SW2_16") (pintype "bidirectional"))
      (node (ref "U$5") (pin "17") (pinfunction "_SW2_17") (pintype "bidirectional"))
      (node (ref "U$6") (pin "P$2") (pinfunction "2_P$2") (pintype "passive"))
    )
    (net (code "97") (name "Net-(U$5-V2P5)") (class "Default")
      (node (ref "C20") (pin "2") (pinfunction "2_2") (pintype "passive"))
      (node (ref "U$5") (pin "21") (pinfunction "V2P5_21") (pintype "bidirectional"))
    )
    (net (code "98") (name "Net-(U$10-BOOST1)") (class "Default")
      (node (ref "C5") (pin "2") (pinfunction "2_2") (pintype "passive"))
      (node (ref "U$10") (pin "23") (pinfunction "BOOST1_23") (pintype "bidirectional"))
    )
    (net (code "99") (name "Net-(U$10-BOOST2)") (class "Default")
      (node (ref "C1") (pin "1") (pinfunction "1_1") (pintype "passive"))
      (node (ref "U$10") (pin "20") (pinfunction "BOOST2_20") (pintype "bidirectional"))
    )
    (net (code "100") (name "Net-(U$10-INTVCC)") (class "Default")
      (node (ref "C14") (pin "2") (pinfunction "2_2") (pintype "passive"))
      (node (ref "U$10") (pin "1") (pinfunction "ITH1_1") (pintype "bidirectional"))
      (node (ref "U$10") (pin "14") (pinfunction "ITH2_14") (pintype "bidirectional"))
      (node (ref "U$10") (pin "21") (pinfunction "V2P5_21") (pintype "bidirectional"))
      (node (ref "U$10") (pin "22") (pinfunction "INTVCC_22") (pintype "bidirectional"))
      (node (ref "U$10") (pin "5") (pinfunction "PHMODE_5") (pintype "bidirectional"))
      (node (ref "U$10") (pin "7") (pinfunction "MODE_7") (pintype "bidirectional"))
    )
    (net (code "101") (name "Net-(U$10-PGOOD1)") (class "Default")
      (node (ref "LED1") (pin "A") (pinfunction "A_A") (pintype "passive"))
      (node (ref "U$10") (pin "4") (pinfunction "PGOOD1_4") (pintype "bidirectional"))
    )
    (net (code "102") (name "Net-(U$10-PGOOD2)") (class "Default")
      (node (ref "LED2") (pin "A") (pinfunction "A_A") (pintype "passive"))
      (node (ref "U$10") (pin "11") (pinfunction "PGOOD2_11") (pintype "bidirectional"))
    )
    (net (code "103") (name "Net-(U$10-RT)") (class "Default")
      (node (ref "R1") (pin "1") (pinfunction "1_1") (pintype "passive"))
      (node (ref "U$10") (pin "8") (pinfunction "RT_8") (pintype "bidirectional"))
    )
    (net (code "104") (name "Net-(U$10-SS1)") (class "Default")
      (node (ref "C35") (pin "2") (pinfunction "2_2") (pintype "passive"))
      (node (ref "U$10") (pin "2") (pinfunction "SS1_2") (pintype "bidirectional"))
    )
    (net (code "105") (name "Net-(U$10-SS2)") (class "Default")
      (node (ref "C37") (pin "2") (pinfunction "2_2") (pintype "passive"))
      (node (ref "U$10") (pin "13") (pinfunction "SS2_13") (pintype "bidirectional"))
    )
    (net (code "106") (name "Net-(U$10-SW1)") (class "Default")
      (node (ref "C5") (pin "1") (pinfunction "1_1") (pintype "passive"))
      (node (ref "U$10") (pin "26") (pinfunction "SW1_26") (pintype "bidirectional"))
      (node (ref "U$10") (pin "27") (pinfunction "_SW1_27") (pintype "bidirectional"))
      (node (ref "U$11") (pin "P$1") (pinfunction "1_P$1") (pintype "passive"))
    )
    (net (code "107") (name "Net-(U$10-SW2)") (class "Default")
      (node (ref "C1") (pin "2") (pinfunction "2_2") (pintype "passive"))
      (node (ref "U$10") (pin "16") (pinfunction "SW2_16") (pintype "bidirectional"))
      (node (ref "U$10") (pin "17") (pinfunction "_SW2_17") (pintype "bidirectional"))
      (node (ref "U$12") (pin "P$1") (pinfunction "1_P$1") (pintype "passive"))
    )
    (net (code "108") (name "Net-(U$10-VFB1)") (class "Default")
      (node (ref "R13") (pin "1") (pinfunction "1_1") (pintype "passive"))
      (node (ref "R8") (pin "1") (pinfunction "1_1") (pintype "passive"))
      (node (ref "U$10") (pin "3") (pinfunction "VFB1_3") (pintype "bidirectional"))
    )
    (net (code "109") (name "Net-(U$10-VFB2)") (class "Default")
      (node (ref "R12") (pin "1") (pinfunction "1_1") (pintype "passive"))
      (node (ref "R9") (pin "1") (pinfunction "1_1") (pintype "passive"))
      (node (ref "U$10") (pin "12") (pinfunction "VFB2_12") (pintype "bidirectional"))
    )
    (net (code "110") (name "Net-(U$23-BST1)") (class "Default")
      (node (ref "C49") (pin "2") (pinfunction "2_2") (pintype "passive"))
      (node (ref "U$23") (pin "26") (pinfunction "BST1_26") (pintype "bidirectional"))
    )
    (net (code "111") (name "Net-(U$23-BST2)") (class "Default")
      (node (ref "C50") (pin "2") (pinfunction "2_2") (pintype "passive"))
      (node (ref "U$23") (pin "3") (pinfunction "BST2_3") (pintype "bidirectional"))
    )
    (net (code "112") (name "Net-(U$23-FB)") (class "Default")
      (node (ref "U$23") (pin "12") (pinfunction "FB_12") (pintype "bidirectional"))
      (node (ref "U$25") (pin "P$2") (pinfunction "WIP_P$2") (pintype "bidirectional"))
    )
    (net (code "113") (name "Net-(U$23-MPPC)") (class "Default")
      (node (ref "C53") (pin "1") (pinfunction "1_1") (pintype "passive"))
      (node (ref "C56") (pin "1") (pinfunction "1_1") (pintype "passive"))
      (node (ref "C57") (pin "1") (pinfunction "1_1") (pintype "passive"))
      (node (ref "LED_G2") (pin "A") (pinfunction "A_A") (pintype "passive"))
      (node (ref "U$23") (pin "11") (pinfunction "SVCC_11") (pintype "bidirectional"))
      (node (ref "U$23") (pin "15") (pinfunction "MPPC_15") (pintype "bidirectional"))
      (node (ref "U$23") (pin "16") (pinfunction "VCC_16") (pintype "bidirectional"))
    )
    (net (code "114") (name "Net-(U$23-RT)") (class "Default")
      (node (ref "R28") (pin "2") (pinfunction "2_2") (pintype "passive"))
      (node (ref "U$23") (pin "17") (pinfunction "RT_17") (pintype "bidirectional"))
    )
    (net (code "115") (name "Net-(U$23-VC)") (class "Default")
      (node (ref "R30") (pin "1") (pinfunction "1_1") (pintype "passive"))
      (node (ref "U$23") (pin "13") (pinfunction "VC_13") (pintype "bidirectional"))
    )
    (net (code "116") (name "Net-(U$59-BST1)") (class "Default")
      (node (ref "C40") (pin "2") (pinfunction "2_2") (pintype "passive"))
      (node (ref "U$59") (pin "26") (pinfunction "BST1_26") (pintype "bidirectional"))
    )
    (net (code "117") (name "Net-(U$59-BST2)") (class "Default")
      (node (ref "C41") (pin "2") (pinfunction "2_2") (pintype "passive"))
      (node (ref "U$59") (pin "3") (pinfunction "BST2_3") (pintype "bidirectional"))
    )
    (net (code "118") (name "Net-(U$59-FB)") (class "Default")
      (node (ref "R70") (pin "1") (pinfunction "1_1") (pintype "passive"))
      (node (ref "R72") (pin "1") (pinfunction "1_1") (pintype "passive"))
      (node (ref "U$59") (pin "12") (pinfunction "FB_12") (pintype "bidirectional"))
    )
    (net (code "119") (name "Net-(U$59-MPPC)") (class "Default")
      (node (ref "R65") (pin "1") (pinfunction "1_1") (pintype "passive"))
      (node (ref "R66") (pin "2") (pinfunction "2_2") (pintype "passive"))
      (node (ref "R67") (pin "2") (pinfunction "2_2") (pintype "passive"))
      (node (ref "U$59") (pin "15") (pinfunction "MPPC_15") (pintype "bidirectional"))
    )
    (net (code "120") (name "Net-(U$59-RT)") (class "Default")
      (node (ref "R68") (pin "2") (pinfunction "2_2") (pintype "passive"))
      (node (ref "U$59") (pin "17") (pinfunction "RT_17") (pintype "bidirectional"))
    )
    (net (code "121") (name "Net-(U$59-SVCC)") (class "Default")
      (node (ref "C45") (pin "1") (pinfunction "1_1") (pintype "passive"))
      (node (ref "LED_G1") (pin "A") (pinfunction "A_A") (pintype "passive"))
      (node (ref "U$59") (pin "11") (pinfunction "SVCC_11") (pintype "bidirectional"))
      (node (ref "U$59") (pin "16") (pinfunction "VCC_16") (pintype "bidirectional"))
    )
    (net (code "122") (name "Net-(U$59-VC)") (class "Default")
      (node (ref "R69") (pin "1") (pinfunction "1_1") (pintype "passive"))
      (node (ref "U$59") (pin "13") (pinfunction "VC_13") (pintype "bidirectional"))
    )
    (net (code "123") (name "unconnected-(INVERT-NC-PadP$1)") (class "Default")
      (node (ref "INVERT") (pin "P$1") (pinfunction "NC_P$1") (pintype "bidirectional"))
    )
  )
)
